# VCFA.net
KiCad netlist of a schematic drawn in EAGLE
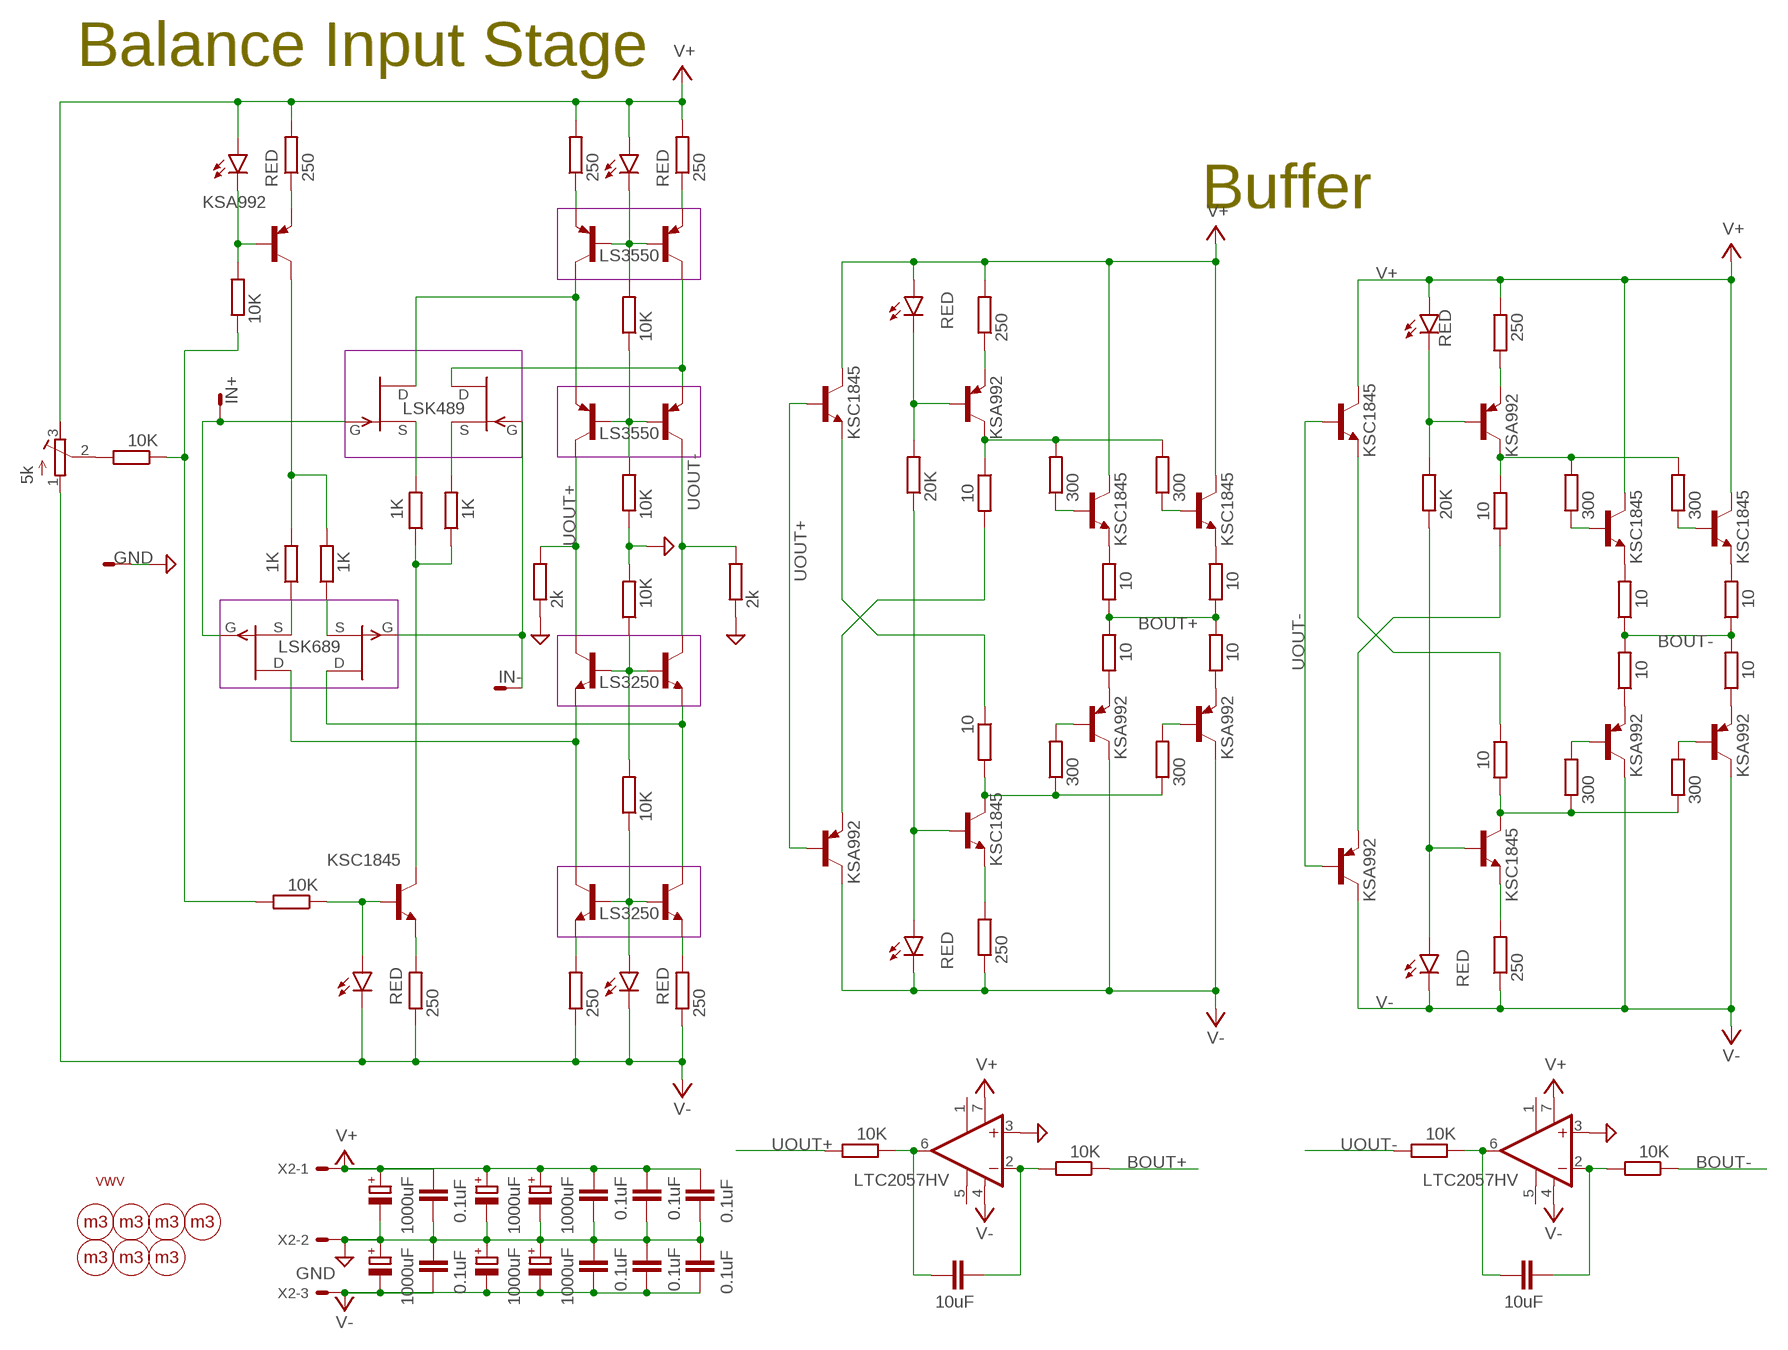
[diagram p0: schematic, sheet 1]
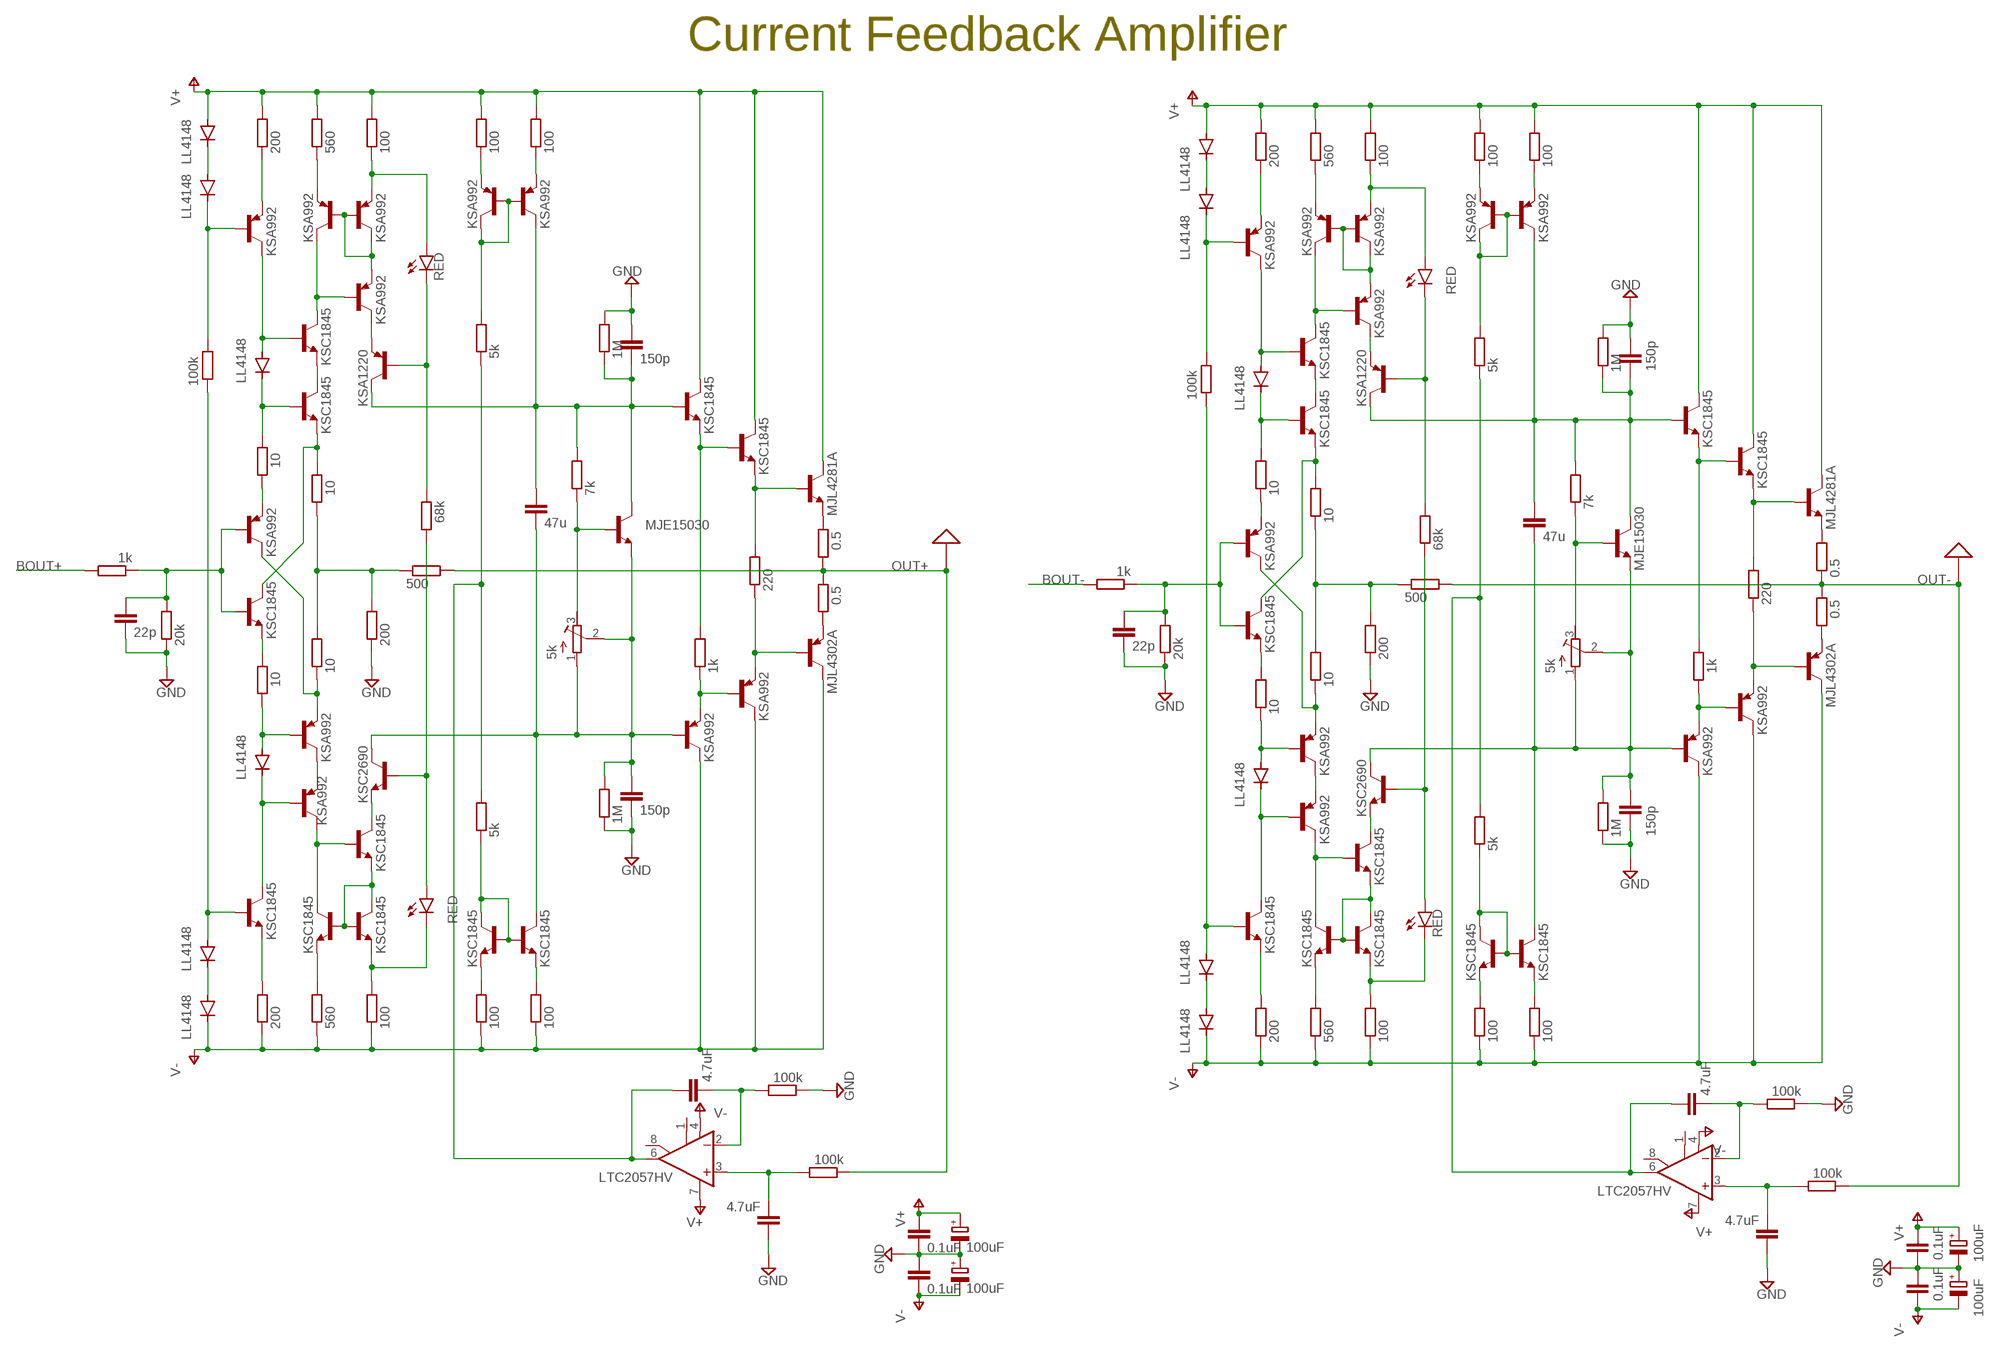
[diagram p1: schematic, sheet 2]
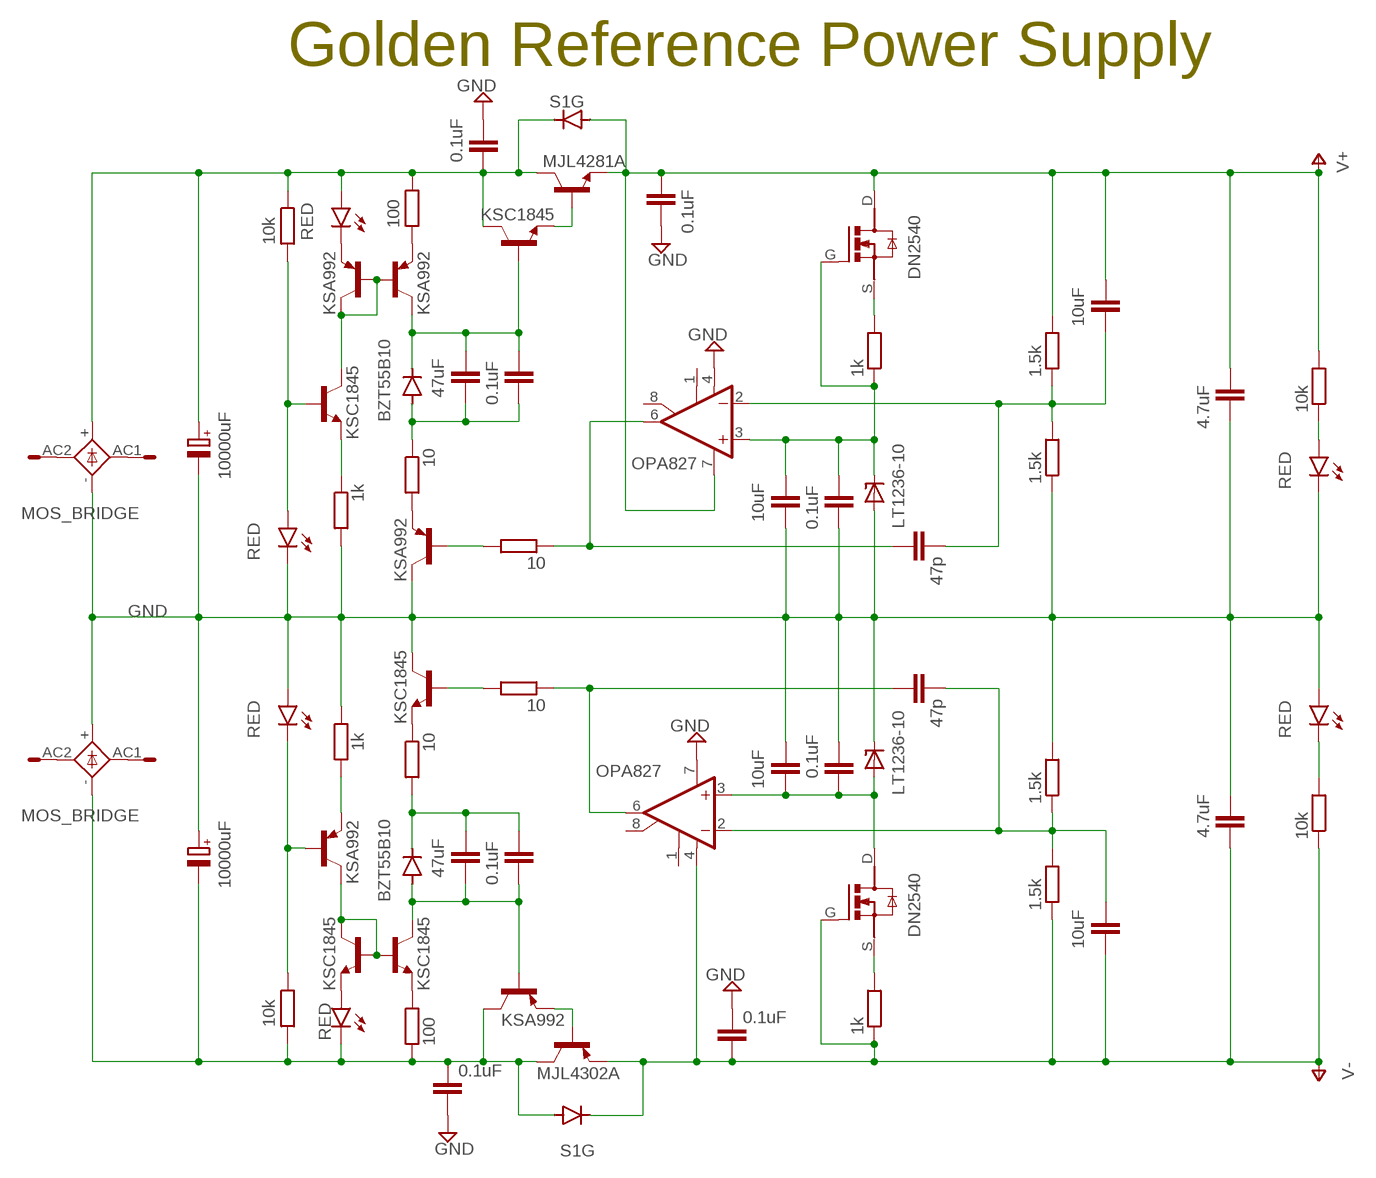
[diagram p2: schematic, sheet 3]

(export (version "E")
  (design (tool "Eeschema 10.0.6"))
  (components
    (comp (ref "C17")
      (value "22p")
      (footprint "eagle-import:C0805")
      (fields (field (name "SPICEPREFIX") "C"))
      (libsource (lib "eagle-import") (part "C-EUC0805"))
    )
    (comp (ref "C18")
      (value "47u")
      (footprint "eagle-import:C1210")
      (fields (field (name "SPICEPREFIX") "C"))
      (libsource (lib "eagle-import") (part "C-EUC1210"))
    )
    (comp (ref "C19")
      (value "150p")
      (footprint "eagle-import:C0805")
      (fields (field (name "SPICEPREFIX") "C"))
      (libsource (lib "eagle-import") (part "C-EUC0805"))
    )
    (comp (ref "C20")
      (value "150p")
      (footprint "eagle-import:C0805")
      (fields (field (name "SPICEPREFIX") "C"))
      (libsource (lib "eagle-import") (part "C-EUC0805"))
    )
    (comp (ref "C21")
      (value "4.7uF")
      (footprint "eagle-import:C1210")
      (fields (field (name "SPICEPREFIX") "C"))
      (libsource (lib "eagle-import") (part "C-EUC1210"))
    )
    (comp (ref "C22")
      (value "4.7uF")
      (footprint "eagle-import:C1210")
      (fields (field (name "SPICEPREFIX") "C"))
      (libsource (lib "eagle-import") (part "C-EUC1210"))
    )
    (comp (ref "C23")
      (value "0.1uF")
      (footprint "eagle-import:C0603K")
      (libsource (lib "eagle-import") (part "C-EUC0603K"))
    )
    (comp (ref "C24")
      (value "0.1uF")
      (footprint "eagle-import:C0603K")
      (libsource (lib "eagle-import") (part "C-EUC0603K"))
    )
    (comp (ref "C25")
      (value "100uF")
      (footprint "eagle-import:E3,5-8")
      (libsource (lib "eagle-import") (part "CPOL-EUE3.5-8"))
    )
    (comp (ref "C26")
      (value "100uF")
      (footprint "eagle-import:E3,5-8")
      (libsource (lib "eagle-import") (part "CPOL-EUE3.5-8"))
    )
    (comp (ref "C27")
      (value "22p")
      (footprint "eagle-import:C0805")
      (fields (field (name "SPICEPREFIX") "C"))
      (libsource (lib "eagle-import") (part "C-EUC0805"))
    )
    (comp (ref "C28")
      (value "47u")
      (footprint "eagle-import:C1210")
      (fields (field (name "SPICEPREFIX") "C"))
      (libsource (lib "eagle-import") (part "C-EUC1210"))
    )
    (comp (ref "C29")
      (value "150p")
      (footprint "eagle-import:C0805")
      (fields (field (name "SPICEPREFIX") "C"))
      (libsource (lib "eagle-import") (part "C-EUC0805"))
    )
    (comp (ref "C30")
      (value "150p")
      (footprint "eagle-import:C0805")
      (fields (field (name "SPICEPREFIX") "C"))
      (libsource (lib "eagle-import") (part "C-EUC0805"))
    )
    (comp (ref "C31")
      (value "4.7uF")
      (footprint "eagle-import:C1210")
      (fields (field (name "SPICEPREFIX") "C"))
      (libsource (lib "eagle-import") (part "C-EUC1210"))
    )
    (comp (ref "C32")
      (value "4.7uF")
      (footprint "eagle-import:C1210")
      (fields (field (name "SPICEPREFIX") "C"))
      (libsource (lib "eagle-import") (part "C-EUC1210"))
    )
    (comp (ref "C33")
      (value "0.1uF")
      (footprint "eagle-import:C0603K")
      (libsource (lib "eagle-import") (part "C-EUC0603K"))
    )
    (comp (ref "C34")
      (value "0.1uF")
      (footprint "eagle-import:C0603K")
      (libsource (lib "eagle-import") (part "C-EUC0603K"))
    )
    (comp (ref "C35")
      (value "100uF")
      (footprint "eagle-import:E3,5-8")
      (libsource (lib "eagle-import") (part "CPOL-EUE3.5-8"))
    )
    (comp (ref "C36")
      (value "100uF")
      (footprint "eagle-import:E3,5-8")
      (libsource (lib "eagle-import") (part "CPOL-EUE3.5-8"))
    )
    (comp (ref "D1")
      (value "LL4148")
      (footprint "eagle-import:SOD80C")
      (fields (field (name "SPICEPREFIX") "D"))
      (libsource (lib "eagle-import") (part "DIODE-SOD80C"))
    )
    (comp (ref "D2")
      (value "LL4148")
      (footprint "eagle-import:SOD80C")
      (fields (field (name "SPICEPREFIX") "D"))
      (libsource (lib "eagle-import") (part "DIODE-SOD80C"))
    )
    (comp (ref "D3")
      (value "LL4148")
      (footprint "eagle-import:SOD80C")
      (fields (field (name "SPICEPREFIX") "D"))
      (libsource (lib "eagle-import") (part "DIODE-SOD80C"))
    )
    (comp (ref "D4")
      (value "LL4148")
      (footprint "eagle-import:SOD80C")
      (fields (field (name "SPICEPREFIX") "D"))
      (libsource (lib "eagle-import") (part "DIODE-SOD80C"))
    )
    (comp (ref "D5")
      (value "LL4148")
      (footprint "eagle-import:SOD80C")
      (fields (field (name "SPICEPREFIX") "D"))
      (libsource (lib "eagle-import") (part "DIODE-SOD80C"))
    )
    (comp (ref "D6")
      (value "LL4148")
      (footprint "eagle-import:SOD80C")
      (fields (field (name "SPICEPREFIX") "D"))
      (libsource (lib "eagle-import") (part "DIODE-SOD80C"))
    )
    (comp (ref "D7")
      (value "LL4148")
      (footprint "eagle-import:SOD80C")
      (fields (field (name "SPICEPREFIX") "D"))
      (libsource (lib "eagle-import") (part "DIODE-SOD80C"))
    )
    (comp (ref "D8")
      (value "LL4148")
      (footprint "eagle-import:SOD80C")
      (fields (field (name "SPICEPREFIX") "D"))
      (libsource (lib "eagle-import") (part "DIODE-SOD80C"))
    )
    (comp (ref "D9")
      (value "LL4148")
      (footprint "eagle-import:SOD80C")
      (fields (field (name "SPICEPREFIX") "D"))
      (libsource (lib "eagle-import") (part "DIODE-SOD80C"))
    )
    (comp (ref "D10")
      (value "LL4148")
      (footprint "eagle-import:SOD80C")
      (fields (field (name "SPICEPREFIX") "D"))
      (libsource (lib "eagle-import") (part "DIODE-SOD80C"))
    )
    (comp (ref "D11")
      (value "LL4148")
      (footprint "eagle-import:SOD80C")
      (fields (field (name "SPICEPREFIX") "D"))
      (libsource (lib "eagle-import") (part "DIODE-SOD80C"))
    )
    (comp (ref "D12")
      (value "LL4148")
      (footprint "eagle-import:SOD80C")
      (fields (field (name "SPICEPREFIX") "D"))
      (libsource (lib "eagle-import") (part "DIODE-SOD80C"))
    )
    (comp (ref "IC3")
      (value "LTC2057HV")
      (footprint "eagle-import:SOIC8")
      (libsource (lib "eagle-import") (part "LT10S837I"))
    )
    (comp (ref "IC4")
      (value "LTC2057HV")
      (footprint "eagle-import:SOIC8")
      (libsource (lib "eagle-import") (part "LT10S837I"))
    )
    (comp (ref "LED9")
      (value "RED")
      (footprint "eagle-import:LED_SML1206")
      (fields (field (name "SPICEPREFIX") "D"))
      (libsource (lib "eagle-import") (part "LEDVWV1206"))
    )
    (comp (ref "LED10")
      (value "RED")
      (footprint "eagle-import:LED_SML1206")
      (fields (field (name "SPICEPREFIX") "D"))
      (libsource (lib "eagle-import") (part "LEDVWV1206"))
    )
    (comp (ref "LED11")
      (value "RED")
      (footprint "eagle-import:LED_SML1206")
      (fields (field (name "SPICEPREFIX") "D"))
      (libsource (lib "eagle-import") (part "LEDVWV1206"))
    )
    (comp (ref "LED12")
      (value "RED")
      (footprint "eagle-import:LED_SML1206")
      (fields (field (name "SPICEPREFIX") "D"))
      (libsource (lib "eagle-import") (part "LEDVWV1206"))
    )
    (comp (ref "PAD1")
      (value "PAD")
      (footprint "eagle-import:PAD-16")
      (libsource (lib "eagle-import") (part "PAD"))
    )
    (comp (ref "PAD2")
      (value "PAD")
      (footprint "eagle-import:PAD-16")
      (libsource (lib "eagle-import") (part "PAD"))
    )
    (comp (ref "Q25")
      (value "KSA992")
      (footprint "eagle-import:TRANSISTOR_TO92-ECB_P")
      (fields (field (name "SPICEPREFIX") "Q"))
      (libsource (lib "eagle-import") (part "BJT_PNPKSA992"))
    )
    (comp (ref "Q26")
      (value "KSA992")
      (footprint "eagle-import:TRANSISTOR_TO92-ECB_P")
      (fields (field (name "SPICEPREFIX") "Q"))
      (libsource (lib "eagle-import") (part "BJT_PNPKSA992"))
    )
    (comp (ref "Q27")
      (value "KSC1845")
      (footprint "eagle-import:TRANSISTOR_TO92-ECB_N")
      (fields (field (name "SPICEPREFIX") "Q"))
      (libsource (lib "eagle-import") (part "BJT_NPNKSC1845"))
    )
    (comp (ref "Q28")
      (value "KSC1845")
      (footprint "eagle-import:TRANSISTOR_TO92-ECB_N")
      (fields (field (name "SPICEPREFIX") "Q"))
      (libsource (lib "eagle-import") (part "BJT_NPNKSC1845"))
    )
    (comp (ref "Q29")
      (value "KSC1845")
      (footprint "eagle-import:TRANSISTOR_TO92-ECB_N")
      (fields (field (name "SPICEPREFIX") "Q"))
      (libsource (lib "eagle-import") (part "BJT_NPNKSC1845"))
    )
    (comp (ref "Q30")
      (value "KSC1845")
      (footprint "eagle-import:TRANSISTOR_TO92-ECB_N")
      (fields (field (name "SPICEPREFIX") "Q"))
      (libsource (lib "eagle-import") (part "BJT_NPNKSC1845"))
    )
    (comp (ref "Q31")
      (value "KSA992")
      (footprint "eagle-import:TRANSISTOR_TO92-ECB_P")
      (fields (field (name "SPICEPREFIX") "Q"))
      (libsource (lib "eagle-import") (part "BJT_PNPKSA992"))
    )
    (comp (ref "Q32")
      (value "KSA992")
      (footprint "eagle-import:TRANSISTOR_TO92-ECB_P")
      (fields (field (name "SPICEPREFIX") "Q"))
      (libsource (lib "eagle-import") (part "BJT_PNPKSA992"))
    )
    (comp (ref "Q33")
      (value "KSA992")
      (footprint "eagle-import:TRANSISTOR_TO92-ECB_P")
      (fields (field (name "SPICEPREFIX") "Q"))
      (libsource (lib "eagle-import") (part "BJT_PNPKSA992"))
    )
    (comp (ref "Q34")
      (value "KSC1845")
      (footprint "eagle-import:TRANSISTOR_TO92-ECB_N")
      (fields (field (name "SPICEPREFIX") "Q"))
      (libsource (lib "eagle-import") (part "BJT_NPNKSC1845"))
    )
    (comp (ref "Q35")
      (value "KSA992")
      (footprint "eagle-import:TRANSISTOR_TO92-ECB_P")
      (fields (field (name "SPICEPREFIX") "Q"))
      (libsource (lib "eagle-import") (part "BJT_PNPKSA992"))
    )
    (comp (ref "Q36")
      (value "KSA992")
      (footprint "eagle-import:TRANSISTOR_TO92-ECB_P")
      (fields (field (name "SPICEPREFIX") "Q"))
      (libsource (lib "eagle-import") (part "BJT_PNPKSA992"))
    )
    (comp (ref "Q37")
      (value "KSC1845")
      (footprint "eagle-import:TRANSISTOR_TO92-ECB_N")
      (fields (field (name "SPICEPREFIX") "Q"))
      (libsource (lib "eagle-import") (part "BJT_NPNKSC1845"))
    )
    (comp (ref "Q38")
      (value "KSC1845")
      (footprint "eagle-import:TRANSISTOR_TO92-ECB_N")
      (fields (field (name "SPICEPREFIX") "Q"))
      (libsource (lib "eagle-import") (part "BJT_NPNKSC1845"))
    )
    (comp (ref "Q39")
      (value "KSA1220")
      (footprint "eagle-import:TRANSISTOR_TO126_P")
      (fields (field (name "SPICEPREFIX") "Q"))
      (libsource (lib "eagle-import") (part "BJT_PNPKSA1220"))
    )
    (comp (ref "Q40")
      (value "KSC2690")
      (footprint "eagle-import:TRANSISTOR_TO126_N")
      (fields (field (name "SPICEPREFIX") "Q"))
      (libsource (lib "eagle-import") (part "BJT_NPNKSC2690"))
    )
    (comp (ref "Q41")
      (value "KSA992")
      (footprint "eagle-import:TRANSISTOR_TO92-ECB_P")
      (fields (field (name "SPICEPREFIX") "Q"))
      (libsource (lib "eagle-import") (part "BJT_PNPKSA992"))
    )
    (comp (ref "Q42")
      (value "KSC1845")
      (footprint "eagle-import:TRANSISTOR_TO92-ECB_N")
      (fields (field (name "SPICEPREFIX") "Q"))
      (libsource (lib "eagle-import") (part "BJT_NPNKSC1845"))
    )
    (comp (ref "Q43")
      (value "KSA992")
      (footprint "eagle-import:TRANSISTOR_TO92-ECB_P")
      (fields (field (name "SPICEPREFIX") "Q"))
      (libsource (lib "eagle-import") (part "BJT_PNPKSA992"))
    )
    (comp (ref "Q44")
      (value "KSC1845")
      (footprint "eagle-import:TRANSISTOR_TO92-ECB_N")
      (fields (field (name "SPICEPREFIX") "Q"))
      (libsource (lib "eagle-import") (part "BJT_NPNKSC1845"))
    )
    (comp (ref "Q45")
      (value "MJE15030")
      (footprint "eagle-import:TRANSISTOR_TO220_BCE_N")
      (fields (field (name "SPICEPREFIX") "Q"))
      (libsource (lib "eagle-import") (part "BJT_NPNMJE15030"))
    )
    (comp (ref "Q46")
      (value "KSC1845")
      (footprint "eagle-import:TRANSISTOR_TO92-ECB_N")
      (fields (field (name "SPICEPREFIX") "Q"))
      (libsource (lib "eagle-import") (part "BJT_NPNKSC1845"))
    )
    (comp (ref "Q47")
      (value "KSA992")
      (footprint "eagle-import:TRANSISTOR_TO92-ECB_P")
      (fields (field (name "SPICEPREFIX") "Q"))
      (libsource (lib "eagle-import") (part "BJT_PNPKSA992"))
    )
    (comp (ref "Q48")
      (value "KSC1845")
      (footprint "eagle-import:TRANSISTOR_TO92-ECB_N")
      (fields (field (name "SPICEPREFIX") "Q"))
      (libsource (lib "eagle-import") (part "BJT_NPNKSC1845"))
    )
    (comp (ref "Q49")
      (value "KSA992")
      (footprint "eagle-import:TRANSISTOR_TO92-ECB_P")
      (fields (field (name "SPICEPREFIX") "Q"))
      (libsource (lib "eagle-import") (part "BJT_PNPKSA992"))
    )
    (comp (ref "Q50")
      (value "MJL4281A")
      (footprint "eagle-import:TRANSISTOR_TO247_BCE_N")
      (fields (field (name "SPICEPREFIX") "Q"))
      (libsource (lib "eagle-import") (part "BJT_NPNMJL4281"))
    )
    (comp (ref "Q51")
      (value "MJL4302A")
      (footprint "eagle-import:TRANSISTOR_TO247_BCE_P")
      (fields (field (name "SPICEPREFIX") "Q"))
      (libsource (lib "eagle-import") (part "BJT_PNPMJL4302"))
    )
    (comp (ref "Q52")
      (value "KSA992")
      (footprint "eagle-import:TRANSISTOR_TO92-ECB_P")
      (fields (field (name "SPICEPREFIX") "Q"))
      (libsource (lib "eagle-import") (part "BJT_PNPKSA992"))
    )
    (comp (ref "Q53")
      (value "KSA992")
      (footprint "eagle-import:TRANSISTOR_TO92-ECB_P")
      (fields (field (name "SPICEPREFIX") "Q"))
      (libsource (lib "eagle-import") (part "BJT_PNPKSA992"))
    )
    (comp (ref "Q54")
      (value "KSC1845")
      (footprint "eagle-import:TRANSISTOR_TO92-ECB_N")
      (fields (field (name "SPICEPREFIX") "Q"))
      (libsource (lib "eagle-import") (part "BJT_NPNKSC1845"))
    )
    (comp (ref "Q55")
      (value "KSC1845")
      (footprint "eagle-import:TRANSISTOR_TO92-ECB_N")
      (fields (field (name "SPICEPREFIX") "Q"))
      (libsource (lib "eagle-import") (part "BJT_NPNKSC1845"))
    )
    (comp (ref "Q56")
      (value "KSC1845")
      (footprint "eagle-import:TRANSISTOR_TO92-ECB_N")
      (fields (field (name "SPICEPREFIX") "Q"))
      (libsource (lib "eagle-import") (part "BJT_NPNKSC1845"))
    )
    (comp (ref "Q57")
      (value "KSC1845")
      (footprint "eagle-import:TRANSISTOR_TO92-ECB_N")
      (fields (field (name "SPICEPREFIX") "Q"))
      (libsource (lib "eagle-import") (part "BJT_NPNKSC1845"))
    )
    (comp (ref "Q58")
      (value "KSA992")
      (footprint "eagle-import:TRANSISTOR_TO92-ECB_P")
      (fields (field (name "SPICEPREFIX") "Q"))
      (libsource (lib "eagle-import") (part "BJT_PNPKSA992"))
    )
    (comp (ref "Q59")
      (value "KSA992")
      (footprint "eagle-import:TRANSISTOR_TO92-ECB_P")
      (fields (field (name "SPICEPREFIX") "Q"))
      (libsource (lib "eagle-import") (part "BJT_PNPKSA992"))
    )
    (comp (ref "Q60")
      (value "KSA992")
      (footprint "eagle-import:TRANSISTOR_TO92-ECB_P")
      (fields (field (name "SPICEPREFIX") "Q"))
      (libsource (lib "eagle-import") (part "BJT_PNPKSA992"))
    )
    (comp (ref "Q61")
      (value "KSC1845")
      (footprint "eagle-import:TRANSISTOR_TO92-ECB_N")
      (fields (field (name "SPICEPREFIX") "Q"))
      (libsource (lib "eagle-import") (part "BJT_NPNKSC1845"))
    )
    (comp (ref "Q62")
      (value "KSA992")
      (footprint "eagle-import:TRANSISTOR_TO92-ECB_P")
      (fields (field (name "SPICEPREFIX") "Q"))
      (libsource (lib "eagle-import") (part "BJT_PNPKSA992"))
    )
    (comp (ref "Q63")
      (value "KSA992")
      (footprint "eagle-import:TRANSISTOR_TO92-ECB_P")
      (fields (field (name "SPICEPREFIX") "Q"))
      (libsource (lib "eagle-import") (part "BJT_PNPKSA992"))
    )
    (comp (ref "Q64")
      (value "KSC1845")
      (footprint "eagle-import:TRANSISTOR_TO92-ECB_N")
      (fields (field (name "SPICEPREFIX") "Q"))
      (libsource (lib "eagle-import") (part "BJT_NPNKSC1845"))
    )
    (comp (ref "Q65")
      (value "KSC1845")
      (footprint "eagle-import:TRANSISTOR_TO92-ECB_N")
      (fields (field (name "SPICEPREFIX") "Q"))
      (libsource (lib "eagle-import") (part "BJT_NPNKSC1845"))
    )
    (comp (ref "Q66")
      (value "KSA1220")
      (footprint "eagle-import:TRANSISTOR_TO126_P")
      (fields (field (name "SPICEPREFIX") "Q"))
      (libsource (lib "eagle-import") (part "BJT_PNPKSA1220"))
    )
    (comp (ref "Q67")
      (value "KSC2690")
      (footprint "eagle-import:TRANSISTOR_TO126_N")
      (fields (field (name "SPICEPREFIX") "Q"))
      (libsource (lib "eagle-import") (part "BJT_NPNKSC2690"))
    )
    (comp (ref "Q68")
      (value "KSA992")
      (footprint "eagle-import:TRANSISTOR_TO92-ECB_P")
      (fields (field (name "SPICEPREFIX") "Q"))
      (libsource (lib "eagle-import") (part "BJT_PNPKSA992"))
    )
    (comp (ref "Q69")
      (value "KSC1845")
      (footprint "eagle-import:TRANSISTOR_TO92-ECB_N")
      (fields (field (name "SPICEPREFIX") "Q"))
      (libsource (lib "eagle-import") (part "BJT_NPNKSC1845"))
    )
    (comp (ref "Q70")
      (value "KSA992")
      (footprint "eagle-import:TRANSISTOR_TO92-ECB_P")
      (fields (field (name "SPICEPREFIX") "Q"))
      (libsource (lib "eagle-import") (part "BJT_PNPKSA992"))
    )
    (comp (ref "Q71")
      (value "KSC1845")
      (footprint "eagle-import:TRANSISTOR_TO92-ECB_N")
      (fields (field (name "SPICEPREFIX") "Q"))
      (libsource (lib "eagle-import") (part "BJT_NPNKSC1845"))
    )
    (comp (ref "Q72")
      (value "MJE15030")
      (footprint "eagle-import:TRANSISTOR_TO220_BCE_N")
      (fields (field (name "SPICEPREFIX") "Q"))
      (libsource (lib "eagle-import") (part "BJT_NPNMJE15030"))
    )
    (comp (ref "Q73")
      (value "KSC1845")
      (footprint "eagle-import:TRANSISTOR_TO92-ECB_N")
      (fields (field (name "SPICEPREFIX") "Q"))
      (libsource (lib "eagle-import") (part "BJT_NPNKSC1845"))
    )
    (comp (ref "Q74")
      (value "KSA992")
      (footprint "eagle-import:TRANSISTOR_TO92-ECB_P")
      (fields (field (name "SPICEPREFIX") "Q"))
      (libsource (lib "eagle-import") (part "BJT_PNPKSA992"))
    )
    (comp (ref "Q75")
      (value "KSC1845")
      (footprint "eagle-import:TRANSISTOR_TO92-ECB_N")
      (fields (field (name "SPICEPREFIX") "Q"))
      (libsource (lib "eagle-import") (part "BJT_NPNKSC1845"))
    )
    (comp (ref "Q76")
      (value "KSA992")
      (footprint "eagle-import:TRANSISTOR_TO92-ECB_P")
      (fields (field (name "SPICEPREFIX") "Q"))
      (libsource (lib "eagle-import") (part "BJT_PNPKSA992"))
    )
    (comp (ref "Q77")
      (value "MJL4281A")
      (footprint "eagle-import:TRANSISTOR_TO247_BCE_N")
      (fields (field (name "SPICEPREFIX") "Q"))
      (libsource (lib "eagle-import") (part "BJT_NPNMJL4281"))
    )
    (comp (ref "Q78")
      (value "MJL4302A")
      (footprint "eagle-import:TRANSISTOR_TO247_BCE_P")
      (fields (field (name "SPICEPREFIX") "Q"))
      (libsource (lib "eagle-import") (part "BJT_PNPMJL4302"))
    )
    (comp (ref "R51")
      (value "1k")
      (footprint "eagle-import:MINI_MELF-0204W")
      (fields (field (name "SPICEPREFIX") "R"))
      (libsource (lib "eagle-import") (part "R-EU_MELF0204W"))
    )
    (comp (ref "R52")
      (value "20k")
      (footprint "eagle-import:MINI_MELF-0204W")
      (fields (field (name "SPICEPREFIX") "R"))
      (libsource (lib "eagle-import") (part "R-EU_MELF0204W"))
    )
    (comp (ref "R53")
      (value "100k")
      (footprint "eagle-import:MINI_MELF-0204W")
      (fields (field (name "SPICEPREFIX") "R"))
      (libsource (lib "eagle-import") (part "R-EU_MELF0204W"))
    )
    (comp (ref "R54")
      (value "200")
      (footprint "eagle-import:MINI_MELF-0204W")
      (fields (field (name "SPICEPREFIX") "R"))
      (libsource (lib "eagle-import") (part "R-EU_MELF0204W"))
    )
    (comp (ref "R55")
      (value "10")
      (footprint "eagle-import:MINI_MELF-0204W")
      (fields (field (name "SPICEPREFIX") "R"))
      (libsource (lib "eagle-import") (part "R-EU_MELF0204W"))
    )
    (comp (ref "R56")
      (value "10")
      (footprint "eagle-import:MINI_MELF-0204W")
      (fields (field (name "SPICEPREFIX") "R"))
      (libsource (lib "eagle-import") (part "R-EU_MELF0204W"))
    )
    (comp (ref "R57")
      (value "200")
      (footprint "eagle-import:MINI_MELF-0204W")
      (fields (field (name "SPICEPREFIX") "R"))
      (libsource (lib "eagle-import") (part "R-EU_MELF0204W"))
    )
    (comp (ref "R58")
      (value "560")
      (footprint "eagle-import:MINI_MELF-0204W")
      (fields (field (name "SPICEPREFIX") "R"))
      (libsource (lib "eagle-import") (part "R-EU_MELF0204W"))
    )
    (comp (ref "R59")
      (value "10")
      (footprint "eagle-import:MINI_MELF-0204W")
      (fields (field (name "SPICEPREFIX") "R"))
      (libsource (lib "eagle-import") (part "R-EU_MELF0204W"))
    )
    (comp (ref "R60")
      (value "10")
      (footprint "eagle-import:MINI_MELF-0204W")
      (fields (field (name "SPICEPREFIX") "R"))
      (libsource (lib "eagle-import") (part "R-EU_MELF0204W"))
    )
    (comp (ref "R61")
      (value "560")
      (footprint "eagle-import:MINI_MELF-0204W")
      (fields (field (name "SPICEPREFIX") "R"))
      (libsource (lib "eagle-import") (part "R-EU_MELF0204W"))
    )
    (comp (ref "R62")
      (value "100")
      (footprint "eagle-import:MINI_MELF-0204W")
      (fields (field (name "SPICEPREFIX") "R"))
      (libsource (lib "eagle-import") (part "R-EU_MELF0204W"))
    )
    (comp (ref "R63")
      (value "200")
      (footprint "eagle-import:MINI_MELF-0204W")
      (fields (field (name "SPICEPREFIX") "R"))
      (libsource (lib "eagle-import") (part "R-EU_MELF0204W"))
    )
    (comp (ref "R64")
      (value "100")
      (footprint "eagle-import:MINI_MELF-0204W")
      (fields (field (name "SPICEPREFIX") "R"))
      (libsource (lib "eagle-import") (part "R-EU_MELF0204W"))
    )
    (comp (ref "R65")
      (value "68k")
      (footprint "eagle-import:MINI_MELF-0204W")
      (fields (field (name "SPICEPREFIX") "R"))
      (libsource (lib "eagle-import") (part "R-EU_MELF0204W"))
    )
    (comp (ref "R66")
      (value "500")
      (footprint "eagle-import:MINI_MELF-0204W")
      (fields (field (name "SPICEPREFIX") "R"))
      (libsource (lib "eagle-import") (part "R-EU_MELF0204W"))
    )
    (comp (ref "R67")
      (value "100")
      (footprint "eagle-import:MINI_MELF-0204W")
      (fields (field (name "SPICEPREFIX") "R"))
      (libsource (lib "eagle-import") (part "R-EU_MELF0204W"))
    )
    (comp (ref "R68")
      (value "5k")
      (footprint "eagle-import:MINI_MELF-0204W")
      (fields (field (name "SPICEPREFIX") "R"))
      (libsource (lib "eagle-import") (part "R-EU_MELF0204W"))
    )
    (comp (ref "R69")
      (value "5k")
      (footprint "eagle-import:MINI_MELF-0204W")
      (fields (field (name "SPICEPREFIX") "R"))
      (libsource (lib "eagle-import") (part "R-EU_MELF0204W"))
    )
    (comp (ref "R70")
      (value "100")
      (footprint "eagle-import:MINI_MELF-0204W")
      (fields (field (name "SPICEPREFIX") "R"))
      (libsource (lib "eagle-import") (part "R-EU_MELF0204W"))
    )
    (comp (ref "R71")
      (value "100")
      (footprint "eagle-import:MINI_MELF-0204W")
      (fields (field (name "SPICEPREFIX") "R"))
      (libsource (lib "eagle-import") (part "R-EU_MELF0204W"))
    )
    (comp (ref "R72")
      (value "100")
      (footprint "eagle-import:MINI_MELF-0204W")
      (fields (field (name "SPICEPREFIX") "R"))
      (libsource (lib "eagle-import") (part "R-EU_MELF0204W"))
    )
    (comp (ref "R73")
      (value "7k")
      (footprint "eagle-import:MINI_MELF-0204W")
      (fields (field (name "SPICEPREFIX") "R"))
      (libsource (lib "eagle-import") (part "R-EU_MELF0204W"))
    )
    (comp (ref "R74")
      (value "5k")
      (footprint "eagle-import:RTRIM3296W")
      (fields (field (name "SPICEPREFIX") "Z"))
      (libsource (lib "eagle-import") (part "R-TRIMM3296W"))
    )
    (comp (ref "R75")
      (value "1M")
      (footprint "eagle-import:MINI_MELF-0204W")
      (fields (field (name "SPICEPREFIX") "R"))
      (libsource (lib "eagle-import") (part "R-EU_MELF0204W"))
    )
    (comp (ref "R76")
      (value "1M")
      (footprint "eagle-import:MINI_MELF-0204W")
      (fields (field (name "SPICEPREFIX") "R"))
      (libsource (lib "eagle-import") (part "R-EU_MELF0204W"))
    )
    (comp (ref "R77")
      (value "1k")
      (footprint "eagle-import:MINI_MELF-0204W")
      (fields (field (name "SPICEPREFIX") "R"))
      (libsource (lib "eagle-import") (part "R-EU_MELF0204W"))
    )
    (comp (ref "R78")
      (value "220")
      (footprint "eagle-import:MINI_MELF-0204W")
      (fields (field (name "SPICEPREFIX") "R"))
      (libsource (lib "eagle-import") (part "R-EU_MELF0204W"))
    )
    (comp (ref "R79")
      (value "100k")
      (footprint "eagle-import:MINI_MELF-0204W")
      (fields (field (name "SPICEPREFIX") "R"))
      (libsource (lib "eagle-import") (part "R-EU_MELF0204W"))
    )
    (comp (ref "R80")
      (value "0.5")
      (footprint "eagle-import:R2512")
      (fields (field (name "SPICEPREFIX") "R"))
      (libsource (lib "eagle-import") (part "R-EU_R2512"))
    )
    (comp (ref "R81")
      (value "0.5")
      (footprint "eagle-import:R2512")
      (fields (field (name "SPICEPREFIX") "R"))
      (libsource (lib "eagle-import") (part "R-EU_R2512"))
    )
    (comp (ref "R82")
      (value "100k")
      (footprint "eagle-import:MINI_MELF-0204W")
      (fields (field (name "SPICEPREFIX") "R"))
      (libsource (lib "eagle-import") (part "R-EU_MELF0204W"))
    )
    (comp (ref "R83")
      (value "1k")
      (footprint "eagle-import:MINI_MELF-0204W")
      (fields (field (name "SPICEPREFIX") "R"))
      (libsource (lib "eagle-import") (part "R-EU_MELF0204W"))
    )
    (comp (ref "R84")
      (value "20k")
      (footprint "eagle-import:MINI_MELF-0204W")
      (fields (field (name "SPICEPREFIX") "R"))
      (libsource (lib "eagle-import") (part "R-EU_MELF0204W"))
    )
    (comp (ref "R85")
      (value "100k")
      (footprint "eagle-import:MINI_MELF-0204W")
      (fields (field (name "SPICEPREFIX") "R"))
      (libsource (lib "eagle-import") (part "R-EU_MELF0204W"))
    )
    (comp (ref "R86")
      (value "200")
      (footprint "eagle-import:MINI_MELF-0204W")
      (fields (field (name "SPICEPREFIX") "R"))
      (libsource (lib "eagle-import") (part "R-EU_MELF0204W"))
    )
    (comp (ref "R87")
      (value "10")
      (footprint "eagle-import:MINI_MELF-0204W")
      (fields (field (name "SPICEPREFIX") "R"))
      (libsource (lib "eagle-import") (part "R-EU_MELF0204W"))
    )
    (comp (ref "R88")
      (value "10")
      (footprint "eagle-import:MINI_MELF-0204W")
      (fields (field (name "SPICEPREFIX") "R"))
      (libsource (lib "eagle-import") (part "R-EU_MELF0204W"))
    )
    (comp (ref "R89")
      (value "200")
      (footprint "eagle-import:MINI_MELF-0204W")
      (fields (field (name "SPICEPREFIX") "R"))
      (libsource (lib "eagle-import") (part "R-EU_MELF0204W"))
    )
    (comp (ref "R90")
      (value "560")
      (footprint "eagle-import:MINI_MELF-0204W")
      (fields (field (name "SPICEPREFIX") "R"))
      (libsource (lib "eagle-import") (part "R-EU_MELF0204W"))
    )
    (comp (ref "R91")
      (value "10")
      (footprint "eagle-import:MINI_MELF-0204W")
      (fields (field (name "SPICEPREFIX") "R"))
      (libsource (lib "eagle-import") (part "R-EU_MELF0204W"))
    )
    (comp (ref "R92")
      (value "10")
      (footprint "eagle-import:MINI_MELF-0204W")
      (fields (field (name "SPICEPREFIX") "R"))
      (libsource (lib "eagle-import") (part "R-EU_MELF0204W"))
    )
    (comp (ref "R93")
      (value "560")
      (footprint "eagle-import:MINI_MELF-0204W")
      (fields (field (name "SPICEPREFIX") "R"))
      (libsource (lib "eagle-import") (part "R-EU_MELF0204W"))
    )
    (comp (ref "R94")
      (value "100")
      (footprint "eagle-import:MINI_MELF-0204W")
      (fields (field (name "SPICEPREFIX") "R"))
      (libsource (lib "eagle-import") (part "R-EU_MELF0204W"))
    )
    (comp (ref "R95")
      (value "200")
      (footprint "eagle-import:MINI_MELF-0204W")
      (fields (field (name "SPICEPREFIX") "R"))
      (libsource (lib "eagle-import") (part "R-EU_MELF0204W"))
    )
    (comp (ref "R96")
      (value "100")
      (footprint "eagle-import:MINI_MELF-0204W")
      (fields (field (name "SPICEPREFIX") "R"))
      (libsource (lib "eagle-import") (part "R-EU_MELF0204W"))
    )
    (comp (ref "R97")
      (value "68k")
      (footprint "eagle-import:MINI_MELF-0204W")
      (fields (field (name "SPICEPREFIX") "R"))
      (libsource (lib "eagle-import") (part "R-EU_MELF0204W"))
    )
    (comp (ref "R98")
      (value "500")
      (footprint "eagle-import:MINI_MELF-0204W")
      (fields (field (name "SPICEPREFIX") "R"))
      (libsource (lib "eagle-import") (part "R-EU_MELF0204W"))
    )
    (comp (ref "R99")
      (value "100")
      (footprint "eagle-import:MINI_MELF-0204W")
      (fields (field (name "SPICEPREFIX") "R"))
      (libsource (lib "eagle-import") (part "R-EU_MELF0204W"))
    )
    (comp (ref "R100")
      (value "5k")
      (footprint "eagle-import:MINI_MELF-0204W")
      (fields (field (name "SPICEPREFIX") "R"))
      (libsource (lib "eagle-import") (part "R-EU_MELF0204W"))
    )
    (comp (ref "R101")
      (value "5k")
      (footprint "eagle-import:MINI_MELF-0204W")
      (fields (field (name "SPICEPREFIX") "R"))
      (libsource (lib "eagle-import") (part "R-EU_MELF0204W"))
    )
    (comp (ref "R102")
      (value "100")
      (footprint "eagle-import:MINI_MELF-0204W")
      (fields (field (name "SPICEPREFIX") "R"))
      (libsource (lib "eagle-import") (part "R-EU_MELF0204W"))
    )
    (comp (ref "R103")
      (value "100")
      (footprint "eagle-import:MINI_MELF-0204W")
      (fields (field (name "SPICEPREFIX") "R"))
      (libsource (lib "eagle-import") (part "R-EU_MELF0204W"))
    )
    (comp (ref "R104")
      (value "100")
      (footprint "eagle-import:MINI_MELF-0204W")
      (fields (field (name "SPICEPREFIX") "R"))
      (libsource (lib "eagle-import") (part "R-EU_MELF0204W"))
    )
    (comp (ref "R105")
      (value "7k")
      (footprint "eagle-import:MINI_MELF-0204W")
      (fields (field (name "SPICEPREFIX") "R"))
      (libsource (lib "eagle-import") (part "R-EU_MELF0204W"))
    )
    (comp (ref "R106")
      (value "5k")
      (footprint "eagle-import:RTRIM3296W")
      (fields (field (name "SPICEPREFIX") "Z"))
      (libsource (lib "eagle-import") (part "R-TRIMM3296W"))
    )
    (comp (ref "R107")
      (value "1M")
      (footprint "eagle-import:MINI_MELF-0204W")
      (fields (field (name "SPICEPREFIX") "R"))
      (libsource (lib "eagle-import") (part "R-EU_MELF0204W"))
    )
    (comp (ref "R108")
      (value "1M")
      (footprint "eagle-import:MINI_MELF-0204W")
      (fields (field (name "SPICEPREFIX") "R"))
      (libsource (lib "eagle-import") (part "R-EU_MELF0204W"))
    )
    (comp (ref "R109")
      (value "1k")
      (footprint "eagle-import:MINI_MELF-0204W")
      (fields (field (name "SPICEPREFIX") "R"))
      (libsource (lib "eagle-import") (part "R-EU_MELF0204W"))
    )
    (comp (ref "R110")
      (value "220")
      (footprint "eagle-import:MINI_MELF-0204W")
      (fields (field (name "SPICEPREFIX") "R"))
      (libsource (lib "eagle-import") (part "R-EU_MELF0204W"))
    )
    (comp (ref "R111")
      (value "100k")
      (footprint "eagle-import:MINI_MELF-0204W")
      (fields (field (name "SPICEPREFIX") "R"))
      (libsource (lib "eagle-import") (part "R-EU_MELF0204W"))
    )
    (comp (ref "R112")
      (value "0.5")
      (footprint "eagle-import:R2512")
      (fields (field (name "SPICEPREFIX") "R"))
      (libsource (lib "eagle-import") (part "R-EU_R2512"))
    )
    (comp (ref "R113")
      (value "0.5")
      (footprint "eagle-import:R2512")
      (fields (field (name "SPICEPREFIX") "R"))
      (libsource (lib "eagle-import") (part "R-EU_R2512"))
    )
    (comp (ref "R114")
      (value "100k")
      (footprint "eagle-import:MINI_MELF-0204W")
      (fields (field (name "SPICEPREFIX") "R"))
      (libsource (lib "eagle-import") (part "R-EU_MELF0204W"))
    )
    (comp (ref "C1")
      (value "1000uF")
      (footprint "eagle-import:E7,5-16")
      (libsource (lib "eagle-import") (part "CPOL-EUE7.5-16"))
    )
    (comp (ref "C2")
      (value "1000uF")
      (footprint "eagle-import:E7,5-16")
      (libsource (lib "eagle-import") (part "CPOL-EUE7.5-16"))
    )
    (comp (ref "C3")
      (value "0.1uF")
      (footprint "eagle-import:C0805")
      (libsource (lib "eagle-import") (part "C-EUC0805"))
    )
    (comp (ref "C4")
      (value "0.1uF")
      (footprint "eagle-import:C0805")
      (libsource (lib "eagle-import") (part "C-EUC0805"))
    )
    (comp (ref "C5")
      (value "1000uF")
      (footprint "eagle-import:E7,5-16")
      (libsource (lib "eagle-import") (part "CPOL-EUE7.5-16"))
    )
    (comp (ref "C6")
      (value "1000uF")
      (footprint "eagle-import:E7,5-16")
      (libsource (lib "eagle-import") (part "CPOL-EUE7.5-16"))
    )
    (comp (ref "C7")
      (value "1000uF")
      (footprint "eagle-import:E7,5-16")
      (libsource (lib "eagle-import") (part "CPOL-EUE7.5-16"))
    )
    (comp (ref "C8")
      (value "1000uF")
      (footprint "eagle-import:E7,5-16")
      (libsource (lib "eagle-import") (part "CPOL-EUE7.5-16"))
    )
    (comp (ref "C9")
      (value "0.1uF")
      (footprint "eagle-import:C050-045X075")
      (libsource (lib "eagle-import") (part "C-EU050-045X075"))
    )
    (comp (ref "C10")
      (value "0.1uF")
      (footprint "eagle-import:C050-045X075")
      (libsource (lib "eagle-import") (part "C-EU050-045X075"))
    )
    (comp (ref "C11")
      (value "0.1uF")
      (footprint "eagle-import:C050-045X075")
      (libsource (lib "eagle-import") (part "C-EU050-045X075"))
    )
    (comp (ref "C12")
      (value "0.1uF")
      (footprint "eagle-import:C050-045X075")
      (libsource (lib "eagle-import") (part "C-EU050-045X075"))
    )
    (comp (ref "C13")
      (value "10uF")
      (footprint "eagle-import:C1206")
      (libsource (lib "eagle-import") (part "C-EUC1206"))
    )
    (comp (ref "C14")
      (value "0.1uF")
      (footprint "eagle-import:C0805")
      (libsource (lib "eagle-import") (part "C-EUC0805"))
    )
    (comp (ref "C15")
      (value "0.1uF")
      (footprint "eagle-import:C0805")
      (libsource (lib "eagle-import") (part "C-EUC0805"))
    )
    (comp (ref "C16")
      (value "10uF")
      (footprint "eagle-import:C1206")
      (libsource (lib "eagle-import") (part "C-EUC1206"))
    )
    (comp (ref "H1")
      (value "HOLE")
      (footprint "eagle-import:M3_HOLE")
      (libsource (lib "eagle-import") (part "HOLE"))
    )
    (comp (ref "H2")
      (value "HOLE")
      (footprint "eagle-import:M3_HOLE")
      (libsource (lib "eagle-import") (part "HOLE"))
    )
    (comp (ref "H3")
      (value "HOLE")
      (footprint "eagle-import:M3_HOLE")
      (libsource (lib "eagle-import") (part "HOLE"))
    )
    (comp (ref "H4")
      (value "HOLE")
      (footprint "eagle-import:M3_HOLE")
      (libsource (lib "eagle-import") (part "HOLE"))
    )
    (comp (ref "H5")
      (value "HOLE")
      (footprint "eagle-import:M3_HOLE")
      (libsource (lib "eagle-import") (part "HOLE"))
    )
    (comp (ref "H6")
      (value "HOLE")
      (footprint "eagle-import:M3_HOLE")
      (libsource (lib "eagle-import") (part "HOLE"))
    )
    (comp (ref "H7")
      (value "HOLE")
      (footprint "eagle-import:M3_HOLE")
      (libsource (lib "eagle-import") (part "HOLE"))
    )
    (comp (ref "IC1")
      (value "LTC2057HV")
      (footprint "eagle-import:SO08")
      (fields (field (name "MF") "TEXAS INSTRUMENTS") (field (name "MPN") "OPA627AU"))
      (libsource (lib "eagle-import") (part "OPA627U"))
    )
    (comp (ref "IC2")
      (value "LTC2057HV")
      (footprint "eagle-import:SO08")
      (fields (field (name "MF") "TEXAS INSTRUMENTS") (field (name "MPN") "OPA627AU"))
      (libsource (lib "eagle-import") (part "OPA627U"))
    )
    (comp (ref "LED1")
      (value "RED")
      (footprint "eagle-import:LED_SML1206")
      (libsource (lib "eagle-import") (part "LEDVWV1206"))
    )
    (comp (ref "LED2")
      (value "RED")
      (footprint "eagle-import:LED_SML1206")
      (fields (field (name "SPICEPREFIX") "D"))
      (libsource (lib "eagle-import") (part "LEDVWV1206"))
    )
    (comp (ref "LED3")
      (value "RED")
      (footprint "eagle-import:LED_SML1206")
      (libsource (lib "eagle-import") (part "LEDVWV1206"))
    )
    (comp (ref "LED4")
      (value "RED")
      (footprint "eagle-import:LED_SML1206")
      (libsource (lib "eagle-import") (part "LEDVWV1206"))
    )
    (comp (ref "LED5")
      (value "RED")
      (footprint "eagle-import:LED_SML1206")
      (libsource (lib "eagle-import") (part "LEDVWV1206"))
    )
    (comp (ref "LED6")
      (value "RED")
      (footprint "eagle-import:LED_SML1206")
      (libsource (lib "eagle-import") (part "LEDVWV1206"))
    )
    (comp (ref "LED7")
      (value "RED")
      (footprint "eagle-import:LED_SML1206")
      (libsource (lib "eagle-import") (part "LEDVWV1206"))
    )
    (comp (ref "LED8")
      (value "RED")
      (footprint "eagle-import:LED_SML1206")
      (libsource (lib "eagle-import") (part "LEDVWV1206"))
    )
    (comp (ref "Q1")
      (value "LSK689")
      (footprint "eagle-import:SOT-23-6")
      (libsource (lib "eagle-import") (part "LSK689"))
    )
    (comp (ref "Q2")
      (value "KSA992")
      (footprint "eagle-import:TRANSISTOR_TO92-ECB_P")
      (libsource (lib "eagle-import") (part "BJT_PNPKSA992"))
    )
    (comp (ref "Q3")
      (value "KSC1845")
      (footprint "eagle-import:TRANSISTOR_TO92-ECB_N")
      (libsource (lib "eagle-import") (part "BJT_NPNKSC1845"))
    )
    (comp (ref "Q4")
      (value "LSK489")
      (footprint "eagle-import:SOT-23-6")
      (libsource (lib "eagle-import") (part "LSK489SOP-6"))
    )
    (comp (ref "Q5")
      (value "LS3550")
      (footprint "eagle-import:SOT-23-6")
      (libsource (lib "eagle-import") (part "LS3550"))
    )
    (comp (ref "Q6")
      (value "LS3250")
      (footprint "eagle-import:SOT-23-6")
      (libsource (lib "eagle-import") (part "LS3250"))
    )
    (comp (ref "Q7")
      (value "LS3250")
      (footprint "eagle-import:SOT-23-6")
      (libsource (lib "eagle-import") (part "LS3250"))
    )
    (comp (ref "Q8")
      (value "LS3550")
      (footprint "eagle-import:SOT-23-6")
      (libsource (lib "eagle-import") (part "LS3550"))
    )
    (comp (ref "Q9")
      (value "KSC1845")
      (footprint "eagle-import:TRANSISTOR_TO92-ECB_N")
      (libsource (lib "eagle-import") (part "BJT_NPNKSC1845"))
    )
    (comp (ref "Q10")
      (value "KSA992")
      (footprint "eagle-import:TRANSISTOR_TO92-ECB_P")
      (libsource (lib "eagle-import") (part "BJT_PNPKSA992"))
    )
    (comp (ref "Q11")
      (value "KSA992")
      (footprint "eagle-import:TRANSISTOR_TO92-ECB_P")
      (libsource (lib "eagle-import") (part "BJT_PNPKSA992"))
    )
    (comp (ref "Q12")
      (value "KSC1845")
      (footprint "eagle-import:TRANSISTOR_TO92-ECB_N")
      (libsource (lib "eagle-import") (part "BJT_NPNKSC1845"))
    )
    (comp (ref "Q13")
      (value "KSC1845")
      (footprint "eagle-import:TRANSISTOR_TO92-ECB_N")
      (libsource (lib "eagle-import") (part "BJT_NPNKSC1845"))
    )
    (comp (ref "Q14")
      (value "KSA992")
      (footprint "eagle-import:TRANSISTOR_TO92-ECB_P")
      (libsource (lib "eagle-import") (part "BJT_PNPKSA992"))
    )
    (comp (ref "Q15")
      (value "KSC1845")
      (footprint "eagle-import:TRANSISTOR_TO92-ECB_N")
      (libsource (lib "eagle-import") (part "BJT_NPNKSC1845"))
    )
    (comp (ref "Q16")
      (value "KSA992")
      (footprint "eagle-import:TRANSISTOR_TO92-ECB_P")
      (libsource (lib "eagle-import") (part "BJT_PNPKSA992"))
    )
    (comp (ref "Q17")
      (value "KSC1845")
      (footprint "eagle-import:TRANSISTOR_TO92-ECB_N")
      (libsource (lib "eagle-import") (part "BJT_NPNKSC1845"))
    )
    (comp (ref "Q18")
      (value "KSA992")
      (footprint "eagle-import:TRANSISTOR_TO92-ECB_P")
      (libsource (lib "eagle-import") (part "BJT_PNPKSA992"))
    )
    (comp (ref "Q19")
      (value "KSA992")
      (footprint "eagle-import:TRANSISTOR_TO92-ECB_P")
      (libsource (lib "eagle-import") (part "BJT_PNPKSA992"))
    )
    (comp (ref "Q20")
      (value "KSC1845")
      (footprint "eagle-import:TRANSISTOR_TO92-ECB_N")
      (libsource (lib "eagle-import") (part "BJT_NPNKSC1845"))
    )
    (comp (ref "Q21")
      (value "KSC1845")
      (footprint "eagle-import:TRANSISTOR_TO92-ECB_N")
      (libsource (lib "eagle-import") (part "BJT_NPNKSC1845"))
    )
    (comp (ref "Q22")
      (value "KSA992")
      (footprint "eagle-import:TRANSISTOR_TO92-ECB_P")
      (libsource (lib "eagle-import") (part "BJT_PNPKSA992"))
    )
    (comp (ref "Q23")
      (value "KSC1845")
      (footprint "eagle-import:TRANSISTOR_TO92-ECB_N")
      (libsource (lib "eagle-import") (part "BJT_NPNKSC1845"))
    )
    (comp (ref "Q24")
      (value "KSA992")
      (footprint "eagle-import:TRANSISTOR_TO92-ECB_P")
      (libsource (lib "eagle-import") (part "BJT_PNPKSA992"))
    )
    (comp (ref "R1")
      (value "5k")
      (footprint "eagle-import:RTRIM3296W")
      (fields (field (name "SPICEPREFIX") "Z"))
      (libsource (lib "eagle-import") (part "R-TRIMM3296W"))
    )
    (comp (ref "R2")
      (value "10K")
      (footprint "eagle-import:MINI_MELF-0204W")
      (libsource (lib "eagle-import") (part "R-EU_MELF0204W"))
    )
    (comp (ref "R3")
      (value "10K")
      (footprint "eagle-import:MINI_MELF-0204W")
      (libsource (lib "eagle-import") (part "R-EU_MELF0204W"))
    )
    (comp (ref "R4")
      (value "10K")
      (footprint "eagle-import:MINI_MELF-0204W")
      (libsource (lib "eagle-import") (part "R-EU_MELF0204W"))
    )
    (comp (ref "R5")
      (value "250")
      (footprint "eagle-import:MINI_MELF-0204W")
      (libsource (lib "eagle-import") (part "R-EU_MELF0204W"))
    )
    (comp (ref "R6")
      (value "1K")
      (footprint "eagle-import:MINI_MELF-0204W")
      (libsource (lib "eagle-import") (part "R-EU_MELF0204W"))
    )
    (comp (ref "R7")
      (value "250")
      (footprint "eagle-import:MINI_MELF-0204W")
      (fields (field (name "SPICEPREFIX") "R"))
      (libsource (lib "eagle-import") (part "R-EU_MELF0204W"))
    )
    (comp (ref "R8")
      (value "1K")
      (footprint "eagle-import:MINI_MELF-0204W")
      (libsource (lib "eagle-import") (part "R-EU_MELF0204W"))
    )
    (comp (ref "R9")
      (value "1K")
      (footprint "eagle-import:MINI_MELF-0204W")
      (libsource (lib "eagle-import") (part "R-EU_MELF0204W"))
    )
    (comp (ref "R10")
      (value "1K")
      (footprint "eagle-import:MINI_MELF-0204W")
      (libsource (lib "eagle-import") (part "R-EU_MELF0204W"))
    )
    (comp (ref "R11")
      (value "2k")
      (footprint "eagle-import:MINI_MELF-0204W")
      (libsource (lib "eagle-import") (part "R-EU_MELF0204W"))
    )
    (comp (ref "R12")
      (value "250")
      (footprint "eagle-import:MINI_MELF-0204W")
      (libsource (lib "eagle-import") (part "R-EU_MELF0204W"))
    )
    (comp (ref "R13")
      (value "250")
      (footprint "eagle-import:MINI_MELF-0204W")
      (libsource (lib "eagle-import") (part "R-EU_MELF0204W"))
    )
    (comp (ref "R14")
      (value "10K")
      (footprint "eagle-import:MINI_MELF-0204W")
      (libsource (lib "eagle-import") (part "R-EU_MELF0204W"))
    )
    (comp (ref "R15")
      (value "10K")
      (footprint "eagle-import:MINI_MELF-0204W")
      (libsource (lib "eagle-import") (part "R-EU_MELF0204W"))
    )
    (comp (ref "R16")
      (value "10K")
      (footprint "eagle-import:MINI_MELF-0204W")
      (libsource (lib "eagle-import") (part "R-EU_MELF0204W"))
    )
    (comp (ref "R17")
      (value "10K")
      (footprint "eagle-import:MINI_MELF-0204W")
      (libsource (lib "eagle-import") (part "R-EU_MELF0204W"))
    )
    (comp (ref "R18")
      (value "250")
      (footprint "eagle-import:MINI_MELF-0204W")
      (libsource (lib "eagle-import") (part "R-EU_MELF0204W"))
    )
    (comp (ref "R19")
      (value "250")
      (footprint "eagle-import:MINI_MELF-0204W")
      (libsource (lib "eagle-import") (part "R-EU_MELF0204W"))
    )
    (comp (ref "R20")
      (value "2k")
      (footprint "eagle-import:MINI_MELF-0204W")
      (libsource (lib "eagle-import") (part "R-EU_MELF0204W"))
    )
    (comp (ref "R21")
      (value "10K")
      (footprint "eagle-import:MINI_MELF-0204W")
      (libsource (lib "eagle-import") (part "R-EU_MELF0204W"))
    )
    (comp (ref "R22")
      (value "20K")
      (footprint "eagle-import:MINI_MELF-0204W")
      (libsource (lib "eagle-import") (part "R-EU_MELF0204W"))
    )
    (comp (ref "R23")
      (value "250")
      (footprint "eagle-import:MINI_MELF-0204W")
      (libsource (lib "eagle-import") (part "R-EU_MELF0204W"))
    )
    (comp (ref "R24")
      (value "10")
      (footprint "eagle-import:MINI_MELF-0204W")
      (libsource (lib "eagle-import") (part "R-EU_MELF0204W"))
    )
    (comp (ref "R25")
      (value "10")
      (footprint "eagle-import:MINI_MELF-0204W")
      (libsource (lib "eagle-import") (part "R-EU_MELF0204W"))
    )
    (comp (ref "R26")
      (value "250")
      (footprint "eagle-import:MINI_MELF-0204W")
      (libsource (lib "eagle-import") (part "R-EU_MELF0204W"))
    )
    (comp (ref "R27")
      (value "300")
      (footprint "eagle-import:MINI_MELF-0204W")
      (libsource (lib "eagle-import") (part "R-EU_MELF0204W"))
    )
    (comp (ref "R28")
      (value "300")
      (footprint "eagle-import:MINI_MELF-0204W")
      (libsource (lib "eagle-import") (part "R-EU_MELF0204W"))
    )
    (comp (ref "R29")
      (value "10K")
      (footprint "eagle-import:MINI_MELF-0204W")
      (libsource (lib "eagle-import") (part "R-EU_MELF0204W"))
    )
    (comp (ref "R30")
      (value "10")
      (footprint "eagle-import:MINI_MELF-0204W")
      (libsource (lib "eagle-import") (part "R-EU_MELF0204W"))
    )
    (comp (ref "R31")
      (value "10")
      (footprint "eagle-import:MINI_MELF-0204W")
      (libsource (lib "eagle-import") (part "R-EU_MELF0204W"))
    )
    (comp (ref "R32")
      (value "300")
      (footprint "eagle-import:MINI_MELF-0204W")
      (libsource (lib "eagle-import") (part "R-EU_MELF0204W"))
    )
    (comp (ref "R33")
      (value "300")
      (footprint "eagle-import:MINI_MELF-0204W")
      (libsource (lib "eagle-import") (part "R-EU_MELF0204W"))
    )
    (comp (ref "R34")
      (value "10")
      (footprint "eagle-import:MINI_MELF-0204W")
      (libsource (lib "eagle-import") (part "R-EU_MELF0204W"))
    )
    (comp (ref "R35")
      (value "10")
      (footprint "eagle-import:MINI_MELF-0204W")
      (libsource (lib "eagle-import") (part "R-EU_MELF0204W"))
    )
    (comp (ref "R36")
      (value "10K")
      (footprint "eagle-import:MINI_MELF-0204W")
      (libsource (lib "eagle-import") (part "R-EU_MELF0204W"))
    )
    (comp (ref "R37")
      (value "20K")
      (footprint "eagle-import:MINI_MELF-0204W")
      (libsource (lib "eagle-import") (part "R-EU_MELF0204W"))
    )
    (comp (ref "R38")
      (value "250")
      (footprint "eagle-import:MINI_MELF-0204W")
      (libsource (lib "eagle-import") (part "R-EU_MELF0204W"))
    )
    (comp (ref "R39")
      (value "10")
      (footprint "eagle-import:MINI_MELF-0204W")
      (libsource (lib "eagle-import") (part "R-EU_MELF0204W"))
    )
    (comp (ref "R40")
      (value "10")
      (footprint "eagle-import:MINI_MELF-0204W")
      (libsource (lib "eagle-import") (part "R-EU_MELF0204W"))
    )
    (comp (ref "R41")
      (value "250")
      (footprint "eagle-import:MINI_MELF-0204W")
      (libsource (lib "eagle-import") (part "R-EU_MELF0204W"))
    )
    (comp (ref "R42")
      (value "300")
      (footprint "eagle-import:MINI_MELF-0204W")
      (libsource (lib "eagle-import") (part "R-EU_MELF0204W"))
    )
    (comp (ref "R43")
      (value "300")
      (footprint "eagle-import:MINI_MELF-0204W")
      (libsource (lib "eagle-import") (part "R-EU_MELF0204W"))
    )
    (comp (ref "R44")
      (value "10K")
      (footprint "eagle-import:MINI_MELF-0204W")
      (libsource (lib "eagle-import") (part "R-EU_MELF0204W"))
    )
    (comp (ref "R45")
      (value "10")
      (footprint "eagle-import:MINI_MELF-0204W")
      (libsource (lib "eagle-import") (part "R-EU_MELF0204W"))
    )
    (comp (ref "R46")
      (value "10")
      (footprint "eagle-import:MINI_MELF-0204W")
      (libsource (lib "eagle-import") (part "R-EU_MELF0204W"))
    )
    (comp (ref "R47")
      (value "300")
      (footprint "eagle-import:MINI_MELF-0204W")
      (libsource (lib "eagle-import") (part "R-EU_MELF0204W"))
    )
    (comp (ref "R48")
      (value "300")
      (footprint "eagle-import:MINI_MELF-0204W")
      (libsource (lib "eagle-import") (part "R-EU_MELF0204W"))
    )
    (comp (ref "R49")
      (value "10")
      (footprint "eagle-import:MINI_MELF-0204W")
      (libsource (lib "eagle-import") (part "R-EU_MELF0204W"))
    )
    (comp (ref "R50")
      (value "10")
      (footprint "eagle-import:MINI_MELF-0204W")
      (libsource (lib "eagle-import") (part "R-EU_MELF0204W"))
    )
    (comp (ref "S1")
      (value "VWV")
      (footprint "eagle-import:VWV")
      (libsource (lib "eagle-import") (part "VWV"))
    )
    (comp (ref "X1")
      (value "KK-156-3")
      (footprint "eagle-import:KK-156-3")
      (fields (field (name "MF") "MOLEX"))
      (libsource (lib "eagle-import") (part "KK-156-3"))
    )
    (comp (ref "X2")
      (value "KK-156-3")
      (footprint "eagle-import:KK-156-3")
      (fields (field (name "MF") "MOLEX"))
      (libsource (lib "eagle-import") (part "KK-156-3"))
    )
    (comp (ref "B1")
      (value "MOS_BRIDGE")
      (footprint "eagle-import:GBU4S")
      (libsource (lib "eagle-import") (part "GBU4"))
    )
    (comp (ref "B2")
      (value "MOS_BRIDGE")
      (footprint "eagle-import:GBU4S")
      (libsource (lib "eagle-import") (part "GBU4"))
    )
    (comp (ref "C37")
      (value "10000uF")
      (footprint "eagle-import:EB35D")
      (libsource (lib "eagle-import") (part "CPOL-EUE10-35"))
    )
    (comp (ref "C38")
      (value "10000uF")
      (footprint "eagle-import:EB35D")
      (libsource (lib "eagle-import") (part "CPOL-EUE10-35"))
    )
    (comp (ref "C39")
      (value "0.1uF")
      (footprint "eagle-import:C050-075X075")
      (libsource (lib "eagle-import") (part "C-EU050-075X075"))
    )
    (comp (ref "C40")
      (value "47uF")
      (footprint "eagle-import:C1206")
      (libsource (lib "eagle-import") (part "C-EUC1206"))
    )
    (comp (ref "C41")
      (value "47uF")
      (footprint "eagle-import:C1206")
      (libsource (lib "eagle-import") (part "C-EUC1206"))
    )
    (comp (ref "C42")
      (value "0.1uF")
      (footprint "eagle-import:C050-075X075")
      (libsource (lib "eagle-import") (part "C-EU050-075X075"))
    )
    (comp (ref "C43")
      (value "0.1uF")
      (footprint "eagle-import:C0805")
      (libsource (lib "eagle-import") (part "C-EUC0805"))
    )
    (comp (ref "C44")
      (value "0.1uF")
      (footprint "eagle-import:C0805")
      (libsource (lib "eagle-import") (part "C-EUC0805"))
    )
    (comp (ref "C45")
      (value "0.1uF")
      (footprint "eagle-import:C0805")
      (libsource (lib "eagle-import") (part "C-EUC0805"))
    )
    (comp (ref "C46")
      (value "0.1uF")
      (footprint "eagle-import:C0805")
      (libsource (lib "eagle-import") (part "C-EUC0805"))
    )
    (comp (ref "C47")
      (value "10uF")
      (footprint "eagle-import:C1206")
      (libsource (lib "eagle-import") (part "C-EUC1206"))
    )
    (comp (ref "C48")
      (value "10uF")
      (footprint "eagle-import:C1206")
      (libsource (lib "eagle-import") (part "C-EUC1206"))
    )
    (comp (ref "C49")
      (value "0.1uF")
      (footprint "eagle-import:C0805")
      (libsource (lib "eagle-import") (part "C-EUC0805"))
    )
    (comp (ref "C50")
      (value "0.1uF")
      (footprint "eagle-import:C0805")
      (libsource (lib "eagle-import") (part "C-EUC0805"))
    )
    (comp (ref "C51")
      (value "47p")
      (footprint "eagle-import:C0805")
      (libsource (lib "eagle-import") (part "C-EUC0805"))
    )
    (comp (ref "C52")
      (value "47p")
      (footprint "eagle-import:C0805")
      (libsource (lib "eagle-import") (part "C-EUC0805"))
    )
    (comp (ref "C53")
      (value "10uF")
      (footprint "eagle-import:C1206")
      (libsource (lib "eagle-import") (part "C-EUC1206"))
    )
    (comp (ref "C54")
      (value "10uF")
      (footprint "eagle-import:C1206")
      (libsource (lib "eagle-import") (part "C-EUC1206"))
    )
    (comp (ref "C55")
      (value "4.7uF")
      (footprint "eagle-import:C050-075X075")
      (libsource (lib "eagle-import") (part "C-EU050-075X075"))
    )
    (comp (ref "C56")
      (value "4.7uF")
      (footprint "eagle-import:C050-075X075")
      (libsource (lib "eagle-import") (part "C-EU050-075X075"))
    )
    (comp (ref "D13")
      (value "BZT55B10")
      (footprint "eagle-import:SOD80C")
      (libsource (lib "eagle-import") (part "DIODE-SOD80C"))
    )
    (comp (ref "D14")
      (value "BZT55B10")
      (footprint "eagle-import:SOD80C")
      (libsource (lib "eagle-import") (part "DIODE-SOD80C"))
    )
    (comp (ref "D15")
      (value "S1G")
      (footprint "eagle-import:DO214AA")
      (libsource (lib "eagle-import") (part "DIODE-DO214AA"))
    )
    (comp (ref "D16")
      (value "S1G")
      (footprint "eagle-import:DO214AA")
      (libsource (lib "eagle-import") (part "DIODE-DO214AA"))
    )
    (comp (ref "D17")
      (value "LT1236-10")
      (footprint "eagle-import:SO8")
      (libsource (lib "eagle-import") (part "LINEAR-TECHNOLOGY_LT1021-VSO-8"))
    )
    (comp (ref "D18")
      (value "LT1236-10")
      (footprint "eagle-import:SO8")
      (libsource (lib "eagle-import") (part "LINEAR-TECHNOLOGY_LT1021-VSO-8"))
    )
    (comp (ref "IC5")
      (value "OPA827")
      (footprint "eagle-import:SOIC8")
      (libsource (lib "eagle-import") (part "LT10S837C"))
    )
    (comp (ref "IC6")
      (value "OPA827")
      (footprint "eagle-import:SOIC8")
      (libsource (lib "eagle-import") (part "LT10S837C"))
    )
    (comp (ref "LED13")
      (value "RED")
      (footprint "eagle-import:LED_SML1206")
      (libsource (lib "eagle-import") (part "LEDVWV1206"))
    )
    (comp (ref "LED14")
      (value "RED")
      (footprint "eagle-import:LED_SML1206")
      (libsource (lib "eagle-import") (part "LEDVWV1206"))
    )
    (comp (ref "LED15")
      (value "RED")
      (footprint "eagle-import:LED_SML1206")
      (libsource (lib "eagle-import") (part "LEDVWV1206"))
    )
    (comp (ref "LED16")
      (value "RED")
      (footprint "eagle-import:LED_SML1206")
      (libsource (lib "eagle-import") (part "LEDVWV1206"))
    )
    (comp (ref "LED17")
      (value "RED")
      (footprint "eagle-import:LED_SML1206")
      (libsource (lib "eagle-import") (part "LEDVWV1206"))
    )
    (comp (ref "LED18")
      (value "RED")
      (footprint "eagle-import:LED_SML1206")
      (libsource (lib "eagle-import") (part "LEDVWV1206"))
    )
    (comp (ref "Q79")
      (value "KSC1845")
      (footprint "eagle-import:TRANSISTOR_TO92-ECB_N")
      (libsource (lib "eagle-import") (part "BJT_NPNKSC1845"))
    )
    (comp (ref "Q80")
      (value "KSA992")
      (footprint "eagle-import:TRANSISTOR_TO92-ECB_P")
      (libsource (lib "eagle-import") (part "BJT_PNPKSA992"))
    )
    (comp (ref "Q81")
      (value "KSA992")
      (footprint "eagle-import:TRANSISTOR_TO92-ECB_P")
      (libsource (lib "eagle-import") (part "BJT_PNPKSA992"))
    )
    (comp (ref "Q82")
      (value "KSC1845")
      (footprint "eagle-import:TRANSISTOR_TO92-ECB_N")
      (libsource (lib "eagle-import") (part "BJT_NPNKSC1845"))
    )
    (comp (ref "Q83")
      (value "KSA992")
      (footprint "eagle-import:TRANSISTOR_TO92-ECB_P")
      (libsource (lib "eagle-import") (part "BJT_PNPKSA992"))
    )
    (comp (ref "Q84")
      (value "KSC1845")
      (footprint "eagle-import:TRANSISTOR_TO92-ECB_N")
      (libsource (lib "eagle-import") (part "BJT_NPNKSC1845"))
    )
    (comp (ref "Q85")
      (value "KSA992")
      (footprint "eagle-import:TRANSISTOR_TO92-ECB_P")
      (libsource (lib "eagle-import") (part "BJT_PNPKSA992"))
    )
    (comp (ref "Q86")
      (value "KSC1845")
      (footprint "eagle-import:TRANSISTOR_TO92-ECB_N")
      (libsource (lib "eagle-import") (part "BJT_NPNKSC1845"))
    )
    (comp (ref "Q87")
      (value "KSC1845")
      (footprint "eagle-import:TRANSISTOR_TO92-ECB_N")
      (libsource (lib "eagle-import") (part "BJT_NPNKSC1845"))
    )
    (comp (ref "Q88")
      (value "KSA992")
      (footprint "eagle-import:TRANSISTOR_TO92-ECB_P")
      (libsource (lib "eagle-import") (part "BJT_PNPKSA992"))
    )
    (comp (ref "Q89")
      (value "MJL4281A")
      (footprint "eagle-import:TRANSISTOR_TO247_BCE_N")
      (libsource (lib "eagle-import") (part "BJT_NPNMJL4281"))
    )
    (comp (ref "Q90")
      (value "MJL4302A")
      (footprint "eagle-import:TRANSISTOR_TO247_BCE_P")
      (libsource (lib "eagle-import") (part "BJT_PNPMJL4302"))
    )
    (comp (ref "Q91")
      (value "DN2540")
      (footprint "eagle-import:TRANSISTOR_TO92-SGD_N")
      (libsource (lib "eagle-import") (part "DN2540"))
    )
    (comp (ref "Q92")
      (value "DN2540")
      (footprint "eagle-import:TRANSISTOR_TO92-SGD_N")
      (libsource (lib "eagle-import") (part "DN2540"))
    )
    (comp (ref "R115")
      (value "10k")
      (footprint "eagle-import:MINI_MELF-0204W")
      (libsource (lib "eagle-import") (part "R-EU_MELF0204W"))
    )
    (comp (ref "R116")
      (value "10k")
      (footprint "eagle-import:MINI_MELF-0204W")
      (libsource (lib "eagle-import") (part "R-EU_MELF0204W"))
    )
    (comp (ref "R117")
      (value "1k")
      (footprint "eagle-import:MINI_MELF-0204W")
      (libsource (lib "eagle-import") (part "R-EU_MELF0204W"))
    )
    (comp (ref "R118")
      (value "1k")
      (footprint "eagle-import:MINI_MELF-0204W")
      (libsource (lib "eagle-import") (part "R-EU_MELF0204W"))
    )
    (comp (ref "R119")
      (value "100")
      (footprint "eagle-import:MINI_MELF-0204W")
      (libsource (lib "eagle-import") (part "R-EU_MELF0204W"))
    )
    (comp (ref "R120")
      (value "10")
      (footprint "eagle-import:MINI_MELF-0204W")
      (libsource (lib "eagle-import") (part "R-EU_MELF0204W"))
    )
    (comp (ref "R121")
      (value "10")
      (footprint "eagle-import:MINI_MELF-0204W")
      (libsource (lib "eagle-import") (part "R-EU_MELF0204W"))
    )
    (comp (ref "R122")
      (value "100")
      (footprint "eagle-import:MINI_MELF-0204W")
      (libsource (lib "eagle-import") (part "R-EU_MELF0204W"))
    )
    (comp (ref "R123")
      (value "10")
      (footprint "eagle-import:MINI_MELF-0204W")
      (libsource (lib "eagle-import") (part "R-EU_MELF0204W"))
    )
    (comp (ref "R124")
      (value "10")
      (footprint "eagle-import:MINI_MELF-0204W")
      (libsource (lib "eagle-import") (part "R-EU_MELF0204W"))
    )
    (comp (ref "R125")
      (value "1k")
      (footprint "eagle-import:MINI_MELF-0204W")
      (libsource (lib "eagle-import") (part "R-EU_MELF0204W"))
    )
    (comp (ref "R126")
      (value "1k")
      (footprint "eagle-import:MINI_MELF-0204W")
      (libsource (lib "eagle-import") (part "R-EU_MELF0204W"))
    )
    (comp (ref "R127")
      (value "1.5k")
      (footprint "eagle-import:MINI_MELF-0204W")
      (libsource (lib "eagle-import") (part "R-EU_MELF0204W"))
    )
    (comp (ref "R128")
      (value "1.5k")
      (footprint "eagle-import:MINI_MELF-0204W")
      (libsource (lib "eagle-import") (part "R-EU_MELF0204W"))
    )
    (comp (ref "R129")
      (value "1.5k")
      (footprint "eagle-import:MINI_MELF-0204W")
      (libsource (lib "eagle-import") (part "R-EU_MELF0204W"))
    )
    (comp (ref "R130")
      (value "1.5k")
      (footprint "eagle-import:MINI_MELF-0204W")
      (libsource (lib "eagle-import") (part "R-EU_MELF0204W"))
    )
    (comp (ref "R131")
      (value "10k")
      (footprint "eagle-import:MINI_MELF-0204W")
      (libsource (lib "eagle-import") (part "R-EU_MELF0204W"))
    )
    (comp (ref "R132")
      (value "10k")
      (footprint "eagle-import:MINI_MELF-0204W")
      (libsource (lib "eagle-import") (part "R-EU_MELF0204W"))
    )
    (comp (ref "X3")
      (value "KK-156-2")
      (footprint "eagle-import:KK-156-2")
      (fields (field (name "MF") "MOLEX"))
      (libsource (lib "eagle-import") (part "KK-156-2"))
    )
    (comp (ref "X4")
      (value "KK-156-2")
      (footprint "eagle-import:KK-156-2")
      (fields (field (name "MF") "MOLEX"))
      (libsource (lib "eagle-import") (part "KK-156-2"))
    )
  )
  (nets
    (net (code "1") (name "BOUT+") (class "Default")
      (node (ref "R29") (pin "1") (pinfunction "1_1") (pintype "passive"))
      (node (ref "R30") (pin "1") (pinfunction "1_1") (pintype "passive"))
      (node (ref "R31") (pin "2") (pinfunction "2_2") (pintype "passive"))
      (node (ref "R34") (pin "1") (pinfunction "1_1") (pintype "passive"))
      (node (ref "R35") (pin "2") (pinfunction "2_2") (pintype "passive"))
      (node (ref "R51") (pin "2") (pinfunction "2_2") (pintype "passive"))
    )
    (net (code "2") (name "BOUT-") (class "Default")
      (node (ref "R44") (pin "1") (pinfunction "1_1") (pintype "passive"))
      (node (ref "R45") (pin "1") (pinfunction "1_1") (pintype "passive"))
      (node (ref "R46") (pin "2") (pinfunction "2_2") (pintype "passive"))
      (node (ref "R49") (pin "1") (pinfunction "1_1") (pintype "passive"))
      (node (ref "R50") (pin "2") (pinfunction "2_2") (pintype "passive"))
      (node (ref "R83") (pin "2") (pinfunction "2_2") (pintype "passive"))
    )
    (net (code "3") (name "GND") (class "Default")
      (node (ref "B1") (pin "-") (pinfunction "-_-") (pintype "passive"))
      (node (ref "B2") (pin "+") (pinfunction "+_+") (pintype "passive"))
      (node (ref "C1") (pin "-") (pinfunction "-_-") (pintype "passive"))
      (node (ref "C10") (pin "1") (pinfunction "1_1") (pintype "passive"))
      (node (ref "C11") (pin "2") (pinfunction "2_2") (pintype "passive"))
      (node (ref "C12") (pin "1") (pinfunction "1_1") (pintype "passive"))
      (node (ref "C14") (pin "1") (pinfunction "1_1") (pintype "passive"))
      (node (ref "C15") (pin "2") (pinfunction "2_2") (pintype "passive"))
      (node (ref "C17") (pin "2") (pinfunction "2_2") (pintype "passive"))
      (node (ref "C19") (pin "1") (pinfunction "1_1") (pintype "passive"))
      (node (ref "C2") (pin "+") (pinfunction "+_+") (pintype "passive"))
      (node (ref "C20") (pin "2") (pinfunction "2_2") (pintype "passive"))
      (node (ref "C22") (pin "1") (pinfunction "1_1") (pintype "passive"))
      (node (ref "C23") (pin "2") (pinfunction "2_2") (pintype "passive"))
      (node (ref "C24") (pin "1") (pinfunction "1_1") (pintype "passive"))
      (node (ref "C25") (pin "-") (pinfunction "-_-") (pintype "passive"))
      (node (ref "C26") (pin "+") (pinfunction "+_+") (pintype "passive"))
      (node (ref "C27") (pin "2") (pinfunction "2_2") (pintype "passive"))
      (node (ref "C29") (pin "1") (pinfunction "1_1") (pintype "passive"))
      (node (ref "C3") (pin "1") (pinfunction "1_1") (pintype "passive"))
      (node (ref "C30") (pin "2") (pinfunction "2_2") (pintype "passive"))
      (node (ref "C32") (pin "1") (pinfunction "1_1") (pintype "passive"))
      (node (ref "C33") (pin "2") (pinfunction "2_2") (pintype "passive"))
      (node (ref "C34") (pin "1") (pinfunction "1_1") (pintype "passive"))
      (node (ref "C35") (pin "-") (pinfunction "-_-") (pintype "passive"))
      (node (ref "C36") (pin "+") (pinfunction "+_+") (pintype "passive"))
      (node (ref "C37") (pin "-") (pinfunction "-_-") (pintype "passive"))
      (node (ref "C38") (pin "+") (pinfunction "+_+") (pintype "passive"))
      (node (ref "C39") (pin "1") (pinfunction "1_1") (pintype "passive"))
      (node (ref "C4") (pin "2") (pinfunction "2_2") (pintype "passive"))
      (node (ref "C42") (pin "2") (pinfunction "2_2") (pintype "passive"))
      (node (ref "C45") (pin "1") (pinfunction "1_1") (pintype "passive"))
      (node (ref "C46") (pin "2") (pinfunction "2_2") (pintype "passive"))
      (node (ref "C47") (pin "2") (pinfunction "2_2") (pintype "passive"))
      (node (ref "C48") (pin "1") (pinfunction "1_1") (pintype "passive"))
      (node (ref "C49") (pin "2") (pinfunction "2_2") (pintype "passive"))
      (node (ref "C5") (pin "-") (pinfunction "-_-") (pintype "passive"))
      (node (ref "C50") (pin "1") (pinfunction "1_1") (pintype "passive"))
      (node (ref "C55") (pin "1") (pinfunction "1_1") (pintype "passive"))
      (node (ref "C56") (pin "2") (pinfunction "2_2") (pintype "passive"))
      (node (ref "C6") (pin "+") (pinfunction "+_+") (pintype "passive"))
      (node (ref "C7") (pin "-") (pinfunction "-_-") (pintype "passive"))
      (node (ref "C8") (pin "+") (pinfunction "+_+") (pintype "passive"))
      (node (ref "C9") (pin "2") (pinfunction "2_2") (pintype "passive"))
      (node (ref "D17") (pin "4") (pinfunction "GND_4") (pintype "passive"))
      (node (ref "D18") (pin "6") (pinfunction "OUT_6") (pintype "passive"))
      (node (ref "IC1") (pin "3") (pinfunction "+IN_3") (pintype "input"))
      (node (ref "IC2") (pin "3") (pinfunction "+IN_3") (pintype "input"))
      (node (ref "IC5") (pin "7") (pinfunction "V+_7") (pintype "power_in"))
      (node (ref "IC6") (pin "4") (pinfunction "V-_4") (pintype "power_in"))
      (node (ref "LED13") (pin "C") (pinfunction "C_C") (pintype "passive"))
      (node (ref "LED14") (pin "A") (pinfunction "A_A") (pintype "passive"))
      (node (ref "LED17") (pin "C") (pinfunction "C_C") (pintype "passive"))
      (node (ref "LED18") (pin "A") (pinfunction "A_A") (pintype "passive"))
      (node (ref "Q85") (pin "C") (pinfunction "C_C") (pintype "passive"))
      (node (ref "Q86") (pin "C") (pinfunction "C_C") (pintype "passive"))
      (node (ref "R107") (pin "2") (pinfunction "2_2") (pintype "passive"))
      (node (ref "R108") (pin "1") (pinfunction "1_1") (pintype "passive"))
      (node (ref "R11") (pin "1") (pinfunction "1_1") (pintype "passive"))
      (node (ref "R111") (pin "1") (pinfunction "1_1") (pintype "passive"))
      (node (ref "R117") (pin "2") (pinfunction "2_2") (pintype "passive"))
      (node (ref "R118") (pin "1") (pinfunction "1_1") (pintype "passive"))
      (node (ref "R128") (pin "1") (pinfunction "1_1") (pintype "passive"))
      (node (ref "R129") (pin "2") (pinfunction "2_2") (pintype "passive"))
      (node (ref "R15") (pin "1") (pinfunction "1_1") (pintype "passive"))
      (node (ref "R16") (pin "2") (pinfunction "2_2") (pintype "passive"))
      (node (ref "R20") (pin "1") (pinfunction "1_1") (pintype "passive"))
      (node (ref "R52") (pin "1") (pinfunction "1_1") (pintype "passive"))
      (node (ref "R63") (pin "1") (pinfunction "1_1") (pintype "passive"))
      (node (ref "R75") (pin "2") (pinfunction "2_2") (pintype "passive"))
      (node (ref "R76") (pin "1") (pinfunction "1_1") (pintype "passive"))
      (node (ref "R79") (pin "1") (pinfunction "1_1") (pintype "passive"))
      (node (ref "R84") (pin "1") (pinfunction "1_1") (pintype "passive"))
      (node (ref "R95") (pin "1") (pinfunction "1_1") (pintype "passive"))
      (node (ref "X1") (pin "2") (pinfunction "S_2") (pintype "passive"))
      (node (ref "X2") (pin "2") (pinfunction "S_2") (pintype "passive"))
    )
    (net (code "4") (name "IN+") (class "Default")
      (node (ref "Q1") (pin "1") (pinfunction "G_1") (pintype "passive"))
      (node (ref "Q4") (pin "1") (pinfunction "G_1") (pintype "passive"))
      (node (ref "X1") (pin "1") (pinfunction "S_1") (pintype "passive"))
    )
    (net (code "5") (name "IN-") (class "Default")
      (node (ref "Q1") (pin "4") (pinfunction "G_4") (pintype "passive"))
      (node (ref "Q4") (pin "4") (pinfunction "G_4") (pintype "passive"))
      (node (ref "X1") (pin "3") (pinfunction "S_3") (pintype "passive"))
    )
    (net (code "6") (name "Net-(B1-AC1)") (class "Default")
      (node (ref "B1") (pin "AC2") (pinfunction "AC1_AC2") (pintype "passive"))
      (node (ref "X3") (pin "1") (pinfunction "S_1") (pintype "passive"))
    )
    (net (code "7") (name "Net-(B1-AC2)") (class "Default")
      (node (ref "B1") (pin "AC1") (pinfunction "AC2_AC1") (pintype "passive"))
      (node (ref "X3") (pin "2") (pinfunction "S_2") (pintype "passive"))
    )
    (net (code "8") (name "Net-(B1-Pad+)") (class "Default")
      (node (ref "B1") (pin "+") (pinfunction "+_+") (pintype "passive"))
      (node (ref "C37") (pin "+") (pinfunction "+_+") (pintype "passive"))
      (node (ref "C42") (pin "1") (pinfunction "1_1") (pintype "passive"))
      (node (ref "D15") (pin "C") (pinfunction "C_C") (pintype "passive"))
      (node (ref "LED15") (pin "A") (pinfunction "A_A") (pintype "passive"))
      (node (ref "Q87") (pin "C") (pinfunction "C_C") (pintype "passive"))
      (node (ref "Q89") (pin "C") (pinfunction "C_C") (pintype "passive"))
      (node (ref "R115") (pin "1") (pinfunction "1_1") (pintype "passive"))
      (node (ref "R119") (pin "1") (pinfunction "1_1") (pintype "passive"))
    )
    (net (code "9") (name "Net-(B2-AC1)") (class "Default")
      (node (ref "B2") (pin "AC2") (pinfunction "AC1_AC2") (pintype "passive"))
      (node (ref "X4") (pin "2") (pinfunction "S_2") (pintype "passive"))
    )
    (net (code "10") (name "Net-(B2-AC2)") (class "Default")
      (node (ref "B2") (pin "AC1") (pinfunction "AC2_AC1") (pintype "passive"))
      (node (ref "X4") (pin "1") (pinfunction "S_1") (pintype "passive"))
    )
    (net (code "11") (name "Net-(B2-Pad-)") (class "Default")
      (node (ref "B2") (pin "-") (pinfunction "-_-") (pintype "passive"))
      (node (ref "C38") (pin "-") (pinfunction "-_-") (pintype "passive"))
      (node (ref "C39") (pin "2") (pinfunction "2_2") (pintype "passive"))
      (node (ref "D16") (pin "A") (pinfunction "A_A") (pintype "passive"))
      (node (ref "LED16") (pin "C") (pinfunction "C_C") (pintype "passive"))
      (node (ref "Q88") (pin "C") (pinfunction "C_C") (pintype "passive"))
      (node (ref "Q90") (pin "C") (pinfunction "C_C") (pintype "passive"))
      (node (ref "R116") (pin "2") (pinfunction "2_2") (pintype "passive"))
      (node (ref "R122") (pin "2") (pinfunction "2_2") (pintype "passive"))
    )
    (net (code "12") (name "Net-(C17-Pad1)") (class "Default")
      (node (ref "C17") (pin "1") (pinfunction "1_1") (pintype "passive"))
      (node (ref "Q26") (pin "B") (pinfunction "B_B") (pintype "passive"))
      (node (ref "Q27") (pin "B") (pinfunction "B_B") (pintype "passive"))
      (node (ref "R51") (pin "1") (pinfunction "1_1") (pintype "passive"))
      (node (ref "R52") (pin "2") (pinfunction "2_2") (pintype "passive"))
    )
    (net (code "13") (name "Net-(C18-Pad1)") (class "Default")
      (node (ref "C18") (pin "1") (pinfunction "1_1") (pintype "passive"))
      (node (ref "C19") (pin "2") (pinfunction "2_2") (pintype "passive"))
      (node (ref "Q39") (pin "C") (pinfunction "C_C") (pintype "passive"))
      (node (ref "Q43") (pin "C") (pinfunction "C_C") (pintype "passive"))
      (node (ref "Q45") (pin "C") (pinfunction "C_C") (pintype "passive"))
      (node (ref "Q46") (pin "B") (pinfunction "B_B") (pintype "passive"))
      (node (ref "R73") (pin "2") (pinfunction "2_2") (pintype "passive"))
      (node (ref "R75") (pin "1") (pinfunction "1_1") (pintype "passive"))
    )
    (net (code "14") (name "Net-(C27-Pad1)") (class "Default")
      (node (ref "C27") (pin "1") (pinfunction "1_1") (pintype "passive"))
      (node (ref "Q53") (pin "B") (pinfunction "B_B") (pintype "passive"))
      (node (ref "Q54") (pin "B") (pinfunction "B_B") (pintype "passive"))
      (node (ref "R83") (pin "1") (pinfunction "1_1") (pintype "passive"))
      (node (ref "R84") (pin "2") (pinfunction "2_2") (pintype "passive"))
    )
    (net (code "15") (name "Net-(C28-Pad1)") (class "Default")
      (node (ref "C28") (pin "1") (pinfunction "1_1") (pintype "passive"))
      (node (ref "C29") (pin "2") (pinfunction "2_2") (pintype "passive"))
      (node (ref "Q66") (pin "C") (pinfunction "C_C") (pintype "passive"))
      (node (ref "Q70") (pin "C") (pinfunction "C_C") (pintype "passive"))
      (node (ref "Q72") (pin "C") (pinfunction "C_C") (pintype "passive"))
      (node (ref "Q73") (pin "B") (pinfunction "B_B") (pintype "passive"))
      (node (ref "R105") (pin "2") (pinfunction "2_2") (pintype "passive"))
      (node (ref "R107") (pin "1") (pinfunction "1_1") (pintype "passive"))
    )
    (net (code "16") (name "Net-(C40-Pad1)") (class "Default")
      (node (ref "C40") (pin "1") (pinfunction "1_1") (pintype "passive"))
      (node (ref "C43") (pin "1") (pinfunction "1_1") (pintype "passive"))
      (node (ref "D13") (pin "C") (pinfunction "C_C") (pintype "passive"))
      (node (ref "Q83") (pin "C") (pinfunction "C_C") (pintype "passive"))
      (node (ref "Q87") (pin "B") (pinfunction "B_B") (pintype "passive"))
    )
    (net (code "17") (name "Net-(C40-Pad2)") (class "Default")
      (node (ref "C40") (pin "2") (pinfunction "2_2") (pintype "passive"))
      (node (ref "C43") (pin "2") (pinfunction "2_2") (pintype "passive"))
      (node (ref "D13") (pin "A") (pinfunction "A_A") (pintype "passive"))
      (node (ref "R120") (pin "1") (pinfunction "1_1") (pintype "passive"))
    )
    (net (code "18") (name "Net-(C41-Pad1)") (class "Default")
      (node (ref "C41") (pin "1") (pinfunction "1_1") (pintype "passive"))
      (node (ref "C44") (pin "1") (pinfunction "1_1") (pintype "passive"))
      (node (ref "D14") (pin "C") (pinfunction "C_C") (pintype "passive"))
      (node (ref "R121") (pin "2") (pinfunction "2_2") (pintype "passive"))
    )
    (net (code "19") (name "Net-(C41-Pad2)") (class "Default")
      (node (ref "C41") (pin "2") (pinfunction "2_2") (pintype "passive"))
      (node (ref "C44") (pin "2") (pinfunction "2_2") (pintype "passive"))
      (node (ref "D14") (pin "A") (pinfunction "A_A") (pintype "passive"))
      (node (ref "Q84") (pin "C") (pinfunction "C_C") (pintype "passive"))
      (node (ref "Q88") (pin "B") (pinfunction "B_B") (pintype "passive"))
    )
    (net (code "20") (name "Net-(D1-PadC)") (class "Default")
      (node (ref "D1") (pin "C") (pinfunction "C_C") (pintype "passive"))
      (node (ref "D2") (pin "A") (pinfunction "A_A") (pintype "passive"))
    )
    (net (code "21") (name "Net-(D2-PadC)") (class "Default")
      (node (ref "D2") (pin "C") (pinfunction "C_C") (pintype "passive"))
      (node (ref "Q25") (pin "B") (pinfunction "B_B") (pintype "passive"))
      (node (ref "R53") (pin "2") (pinfunction "2_2") (pintype "passive"))
    )
    (net (code "22") (name "Net-(D3-PadA)") (class "Default")
      (node (ref "D3") (pin "A") (pinfunction "A_A") (pintype "passive"))
      (node (ref "Q28") (pin "B") (pinfunction "B_B") (pintype "passive"))
      (node (ref "R53") (pin "1") (pinfunction "1_1") (pintype "passive"))
    )
    (net (code "23") (name "Net-(D3-PadC)") (class "Default")
      (node (ref "D3") (pin "C") (pinfunction "C_C") (pintype "passive"))
      (node (ref "D4") (pin "A") (pinfunction "A_A") (pintype "passive"))
    )
    (net (code "24") (name "Net-(D5-PadA)") (class "Default")
      (node (ref "D5") (pin "A") (pinfunction "A_A") (pintype "passive"))
      (node (ref "Q25") (pin "C") (pinfunction "C_C") (pintype "passive"))
      (node (ref "Q29") (pin "B") (pinfunction "B_B") (pintype "passive"))
    )
    (net (code "25") (name "Net-(D5-PadC)") (class "Default")
      (node (ref "D5") (pin "C") (pinfunction "C_C") (pintype "passive"))
      (node (ref "Q30") (pin "B") (pinfunction "B_B") (pintype "passive"))
      (node (ref "R55") (pin "2") (pinfunction "2_2") (pintype "passive"))
    )
    (net (code "26") (name "Net-(D6-PadA)") (class "Default")
      (node (ref "D6") (pin "A") (pinfunction "A_A") (pintype "passive"))
      (node (ref "Q31") (pin "B") (pinfunction "B_B") (pintype "passive"))
      (node (ref "R56") (pin "1") (pinfunction "1_1") (pintype "passive"))
    )
    (net (code "27") (name "Net-(D6-PadC)") (class "Default")
      (node (ref "D6") (pin "C") (pinfunction "C_C") (pintype "passive"))
      (node (ref "Q28") (pin "C") (pinfunction "C_C") (pintype "passive"))
      (node (ref "Q32") (pin "B") (pinfunction "B_B") (pintype "passive"))
    )
    (net (code "28") (name "Net-(D7-PadC)") (class "Default")
      (node (ref "D7") (pin "C") (pinfunction "C_C") (pintype "passive"))
      (node (ref "D8") (pin "A") (pinfunction "A_A") (pintype "passive"))
    )
    (net (code "29") (name "Net-(D8-PadC)") (class "Default")
      (node (ref "D8") (pin "C") (pinfunction "C_C") (pintype "passive"))
      (node (ref "Q52") (pin "B") (pinfunction "B_B") (pintype "passive"))
      (node (ref "R85") (pin "2") (pinfunction "2_2") (pintype "passive"))
    )
    (net (code "30") (name "Net-(D9-PadA)") (class "Default")
      (node (ref "D9") (pin "A") (pinfunction "A_A") (pintype "passive"))
      (node (ref "Q55") (pin "B") (pinfunction "B_B") (pintype "passive"))
      (node (ref "R85") (pin "1") (pinfunction "1_1") (pintype "passive"))
    )
    (net (code "31") (name "Net-(D10-PadA)") (class "Default")
      (node (ref "D10") (pin "A") (pinfunction "A_A") (pintype "passive"))
      (node (ref "D9") (pin "C") (pinfunction "C_C") (pintype "passive"))
    )
    (net (code "32") (name "Net-(D11-PadA)") (class "Default")
      (node (ref "D11") (pin "A") (pinfunction "A_A") (pintype "passive"))
      (node (ref "Q52") (pin "C") (pinfunction "C_C") (pintype "passive"))
      (node (ref "Q56") (pin "B") (pinfunction "B_B") (pintype "passive"))
    )
    (net (code "33") (name "Net-(D11-PadC)") (class "Default")
      (node (ref "D11") (pin "C") (pinfunction "C_C") (pintype "passive"))
      (node (ref "Q57") (pin "B") (pinfunction "B_B") (pintype "passive"))
      (node (ref "R87") (pin "2") (pinfunction "2_2") (pintype "passive"))
    )
    (net (code "34") (name "Net-(D12-PadA)") (class "Default")
      (node (ref "D12") (pin "A") (pinfunction "A_A") (pintype "passive"))
      (node (ref "Q58") (pin "B") (pinfunction "B_B") (pintype "passive"))
      (node (ref "R88") (pin "1") (pinfunction "1_1") (pintype "passive"))
    )
    (net (code "35") (name "Net-(D12-PadC)") (class "Default")
      (node (ref "D12") (pin "C") (pinfunction "C_C") (pintype "passive"))
      (node (ref "Q55") (pin "C") (pinfunction "C_C") (pintype "passive"))
      (node (ref "Q59") (pin "B") (pinfunction "B_B") (pintype "passive"))
    )
    (net (code "36") (name "Net-(D17-OUT)") (class "Default")
      (node (ref "C47") (pin "1") (pinfunction "1_1") (pintype "passive"))
      (node (ref "C49") (pin "1") (pinfunction "1_1") (pintype "passive"))
      (node (ref "D17") (pin "6") (pinfunction "OUT_6") (pintype "passive"))
      (node (ref "IC6") (pin "3") (pinfunction "+IN_3") (pintype "input"))
      (node (ref "Q91") (pin "G") (pinfunction "G_G") (pintype "passive"))
      (node (ref "R125") (pin "1") (pinfunction "1_1") (pintype "passive"))
    )
    (net (code "37") (name "Net-(D18-GND)") (class "Default")
      (node (ref "C48") (pin "2") (pinfunction "2_2") (pintype "passive"))
      (node (ref "C50") (pin "2") (pinfunction "2_2") (pintype "passive"))
      (node (ref "D18") (pin "4") (pinfunction "GND_4") (pintype "passive"))
      (node (ref "IC5") (pin "3") (pinfunction "+IN_3") (pintype "input"))
      (node (ref "Q92") (pin "D") (pinfunction "D_D") (pintype "passive"))
    )
    (net (code "38") (name "Net-(IC1--IN)") (class "Default")
      (node (ref "C13") (pin "2") (pinfunction "2_2") (pintype "passive"))
      (node (ref "IC1") (pin "2") (pinfunction "-IN_2") (pintype "input"))
      (node (ref "R29") (pin "2") (pinfunction "2_2") (pintype "passive"))
    )
    (net (code "39") (name "Net-(IC1-OUT)") (class "Default")
      (node (ref "C13") (pin "1") (pinfunction "1_1") (pintype "passive"))
      (node (ref "IC1") (pin "6") (pinfunction "OUT_6") (pintype "output"))
      (node (ref "R21") (pin "1") (pinfunction "1_1") (pintype "passive"))
    )
    (net (code "40") (name "Net-(IC2--IN)") (class "Default")
      (node (ref "C16") (pin "2") (pinfunction "2_2") (pintype "passive"))
      (node (ref "IC2") (pin "2") (pinfunction "-IN_2") (pintype "input"))
      (node (ref "R44") (pin "2") (pinfunction "2_2") (pintype "passive"))
    )
    (net (code "41") (name "Net-(IC2-OUT)") (class "Default")
      (node (ref "C16") (pin "1") (pinfunction "1_1") (pintype "passive"))
      (node (ref "IC2") (pin "6") (pinfunction "OUT_6") (pintype "output"))
      (node (ref "R36") (pin "1") (pinfunction "1_1") (pintype "passive"))
    )
    (net (code "42") (name "Net-(IC3-+IN)") (class "Default")
      (node (ref "C22") (pin "2") (pinfunction "2_2") (pintype "passive"))
      (node (ref "IC3") (pin "3") (pinfunction "+IN_3") (pintype "input"))
      (node (ref "R82") (pin "2") (pinfunction "2_2") (pintype "passive"))
    )
    (net (code "43") (name "Net-(IC3--IN)") (class "Default")
      (node (ref "C21") (pin "2") (pinfunction "2_2") (pintype "passive"))
      (node (ref "IC3") (pin "2") (pinfunction "-IN_2") (pintype "input"))
      (node (ref "R79") (pin "2") (pinfunction "2_2") (pintype "passive"))
    )
    (net (code "44") (name "Net-(IC3-OUT)") (class "Default")
      (node (ref "C21") (pin "1") (pinfunction "1_1") (pintype "passive"))
      (node (ref "IC3") (pin "6") (pinfunction "OUT_6") (pintype "output"))
      (node (ref "R68") (pin "1") (pinfunction "1_1") (pintype "passive"))
      (node (ref "R69") (pin "2") (pinfunction "2_2") (pintype "passive"))
    )
    (net (code "45") (name "Net-(IC4-+IN)") (class "Default")
      (node (ref "C32") (pin "2") (pinfunction "2_2") (pintype "passive"))
      (node (ref "IC4") (pin "3") (pinfunction "+IN_3") (pintype "input"))
      (node (ref "R114") (pin "2") (pinfunction "2_2") (pintype "passive"))
    )
    (net (code "46") (name "Net-(IC4--IN)") (class "Default")
      (node (ref "C31") (pin "2") (pinfunction "2_2") (pintype "passive"))
      (node (ref "IC4") (pin "2") (pinfunction "-IN_2") (pintype "input"))
      (node (ref "R111") (pin "2") (pinfunction "2_2") (pintype "passive"))
    )
    (net (code "47") (name "Net-(IC4-OUT)") (class "Default")
      (node (ref "C31") (pin "1") (pinfunction "1_1") (pintype "passive"))
      (node (ref "IC4") (pin "6") (pinfunction "OUT_6") (pintype "output"))
      (node (ref "R100") (pin "1") (pinfunction "1_1") (pintype "passive"))
      (node (ref "R101") (pin "2") (pinfunction "2_2") (pintype "passive"))
    )
    (net (code "48") (name "Net-(IC5--IN)") (class "Default")
      (node (ref "C52") (pin "2") (pinfunction "2_2") (pintype "passive"))
      (node (ref "C54") (pin "1") (pinfunction "1_1") (pintype "passive"))
      (node (ref "IC5") (pin "2") (pinfunction "-IN_2") (pintype "input"))
      (node (ref "R129") (pin "1") (pinfunction "1_1") (pintype "passive"))
      (node (ref "R130") (pin "2") (pinfunction "2_2") (pintype "passive"))
    )
    (net (code "49") (name "Net-(IC5-OUT)") (class "Default")
      (node (ref "C52") (pin "1") (pinfunction "1_1") (pintype "passive"))
      (node (ref "IC5") (pin "6") (pinfunction "OUT_6") (pintype "output"))
      (node (ref "R124") (pin "1") (pinfunction "1_1") (pintype "passive"))
    )
    (net (code "50") (name "Net-(IC6--IN)") (class "Default")
      (node (ref "C51") (pin "2") (pinfunction "2_2") (pintype "passive"))
      (node (ref "C53") (pin "2") (pinfunction "2_2") (pintype "passive"))
      (node (ref "IC6") (pin "2") (pinfunction "-IN_2") (pintype "input"))
      (node (ref "R127") (pin "1") (pinfunction "1_1") (pintype "passive"))
      (node (ref "R128") (pin "2") (pinfunction "2_2") (pintype "passive"))
    )
    (net (code "51") (name "Net-(IC6-OUT)") (class "Default")
      (node (ref "C51") (pin "1") (pinfunction "1_1") (pintype "passive"))
      (node (ref "IC6") (pin "6") (pinfunction "OUT_6") (pintype "output"))
      (node (ref "R123") (pin "1") (pinfunction "1_1") (pintype "passive"))
    )
    (net (code "52") (name "Net-(LED1-PadC)") (class "Default")
      (node (ref "LED1") (pin "C") (pinfunction "C_C") (pintype "passive"))
      (node (ref "Q2") (pin "B") (pinfunction "B_B") (pintype "passive"))
      (node (ref "R3") (pin "2") (pinfunction "2_2") (pintype "passive"))
    )
    (net (code "53") (name "Net-(LED2-PadA)") (class "Default")
      (node (ref "LED2") (pin "A") (pinfunction "A_A") (pintype "passive"))
      (node (ref "Q3") (pin "B") (pinfunction "B_B") (pintype "passive"))
      (node (ref "R4") (pin "1") (pinfunction "1_1") (pintype "passive"))
    )
    (net (code "54") (name "Net-(LED5-PadC)") (class "Default")
      (node (ref "LED5") (pin "C") (pinfunction "C_C") (pintype "passive"))
      (node (ref "Q11") (pin "B") (pinfunction "B_B") (pintype "passive"))
      (node (ref "R22") (pin "2") (pinfunction "2_2") (pintype "passive"))
    )
    (net (code "55") (name "Net-(LED6-PadA)") (class "Default")
      (node (ref "LED6") (pin "A") (pinfunction "A_A") (pintype "passive"))
      (node (ref "Q12") (pin "B") (pinfunction "B_B") (pintype "passive"))
      (node (ref "R22") (pin "1") (pinfunction "1_1") (pintype "passive"))
    )
    (net (code "56") (name "Net-(LED7-PadC)") (class "Default")
      (node (ref "LED7") (pin "C") (pinfunction "C_C") (pintype "passive"))
      (node (ref "Q19") (pin "B") (pinfunction "B_B") (pintype "passive"))
      (node (ref "R37") (pin "2") (pinfunction "2_2") (pintype "passive"))
    )
    (net (code "57") (name "Net-(LED8-PadA)") (class "Default")
      (node (ref "LED8") (pin "A") (pinfunction "A_A") (pintype "passive"))
      (node (ref "Q20") (pin "B") (pinfunction "B_B") (pintype "passive"))
      (node (ref "R37") (pin "1") (pinfunction "1_1") (pintype "passive"))
    )
    (net (code "58") (name "Net-(LED9-PadA)") (class "Default")
      (node (ref "LED9") (pin "A") (pinfunction "A_A") (pintype "passive"))
      (node (ref "Q35") (pin "E") (pinfunction "E_E") (pintype "passive"))
      (node (ref "R62") (pin "1") (pinfunction "1_1") (pintype "passive"))
    )
    (net (code "59") (name "Net-(LED9-PadC)") (class "Default")
      (node (ref "LED9") (pin "C") (pinfunction "C_C") (pintype "passive"))
      (node (ref "Q39") (pin "B") (pinfunction "B_B") (pintype "passive"))
      (node (ref "R65") (pin "2") (pinfunction "2_2") (pintype "passive"))
    )
    (net (code "60") (name "Net-(LED10-PadA)") (class "Default")
      (node (ref "LED10") (pin "A") (pinfunction "A_A") (pintype "passive"))
      (node (ref "Q40") (pin "B") (pinfunction "B_B") (pintype "passive"))
      (node (ref "R65") (pin "1") (pinfunction "1_1") (pintype "passive"))
    )
    (net (code "61") (name "Net-(LED10-PadC)") (class "Default")
      (node (ref "LED10") (pin "C") (pinfunction "C_C") (pintype "passive"))
      (node (ref "Q38") (pin "E") (pinfunction "E_E") (pintype "passive"))
      (node (ref "R64") (pin "2") (pinfunction "2_2") (pintype "passive"))
    )
    (net (code "62") (name "Net-(LED11-PadA)") (class "Default")
      (node (ref "LED11") (pin "A") (pinfunction "A_A") (pintype "passive"))
      (node (ref "Q62") (pin "E") (pinfunction "E_E") (pintype "passive"))
      (node (ref "R94") (pin "1") (pinfunction "1_1") (pintype "passive"))
    )
    (net (code "63") (name "Net-(LED11-PadC)") (class "Default")
      (node (ref "LED11") (pin "C") (pinfunction "C_C") (pintype "passive"))
      (node (ref "Q66") (pin "B") (pinfunction "B_B") (pintype "passive"))
      (node (ref "R97") (pin "2") (pinfunction "2_2") (pintype "passive"))
    )
    (net (code "64") (name "Net-(LED12-PadA)") (class "Default")
      (node (ref "LED12") (pin "A") (pinfunction "A_A") (pintype "passive"))
      (node (ref "Q67") (pin "B") (pinfunction "B_B") (pintype "passive"))
      (node (ref "R97") (pin "1") (pinfunction "1_1") (pintype "passive"))
    )
    (net (code "65") (name "Net-(LED12-PadC)") (class "Default")
      (node (ref "LED12") (pin "C") (pinfunction "C_C") (pintype "passive"))
      (node (ref "Q65") (pin "E") (pinfunction "E_E") (pintype "passive"))
      (node (ref "R96") (pin "2") (pinfunction "2_2") (pintype "passive"))
    )
    (net (code "66") (name "Net-(LED13-PadA)") (class "Default")
      (node (ref "LED13") (pin "A") (pinfunction "A_A") (pintype "passive"))
      (node (ref "Q79") (pin "B") (pinfunction "B_B") (pintype "passive"))
      (node (ref "R115") (pin "2") (pinfunction "2_2") (pintype "passive"))
    )
    (net (code "67") (name "Net-(LED14-PadC)") (class "Default")
      (node (ref "LED14") (pin "C") (pinfunction "C_C") (pintype "passive"))
      (node (ref "Q80") (pin "B") (pinfunction "B_B") (pintype "passive"))
      (node (ref "R116") (pin "1") (pinfunction "1_1") (pintype "passive"))
    )
    (net (code "68") (name "Net-(LED15-PadC)") (class "Default")
      (node (ref "LED15") (pin "C") (pinfunction "C_C") (pintype "passive"))
      (node (ref "Q81") (pin "E") (pinfunction "E_E") (pintype "passive"))
    )
    (net (code "69") (name "Net-(LED16-PadA)") (class "Default")
      (node (ref "LED16") (pin "A") (pinfunction "A_A") (pintype "passive"))
      (node (ref "Q82") (pin "E") (pinfunction "E_E") (pintype "passive"))
    )
    (net (code "70") (name "Net-(LED17-PadA)") (class "Default")
      (node (ref "LED17") (pin "A") (pinfunction "A_A") (pintype "passive"))
      (node (ref "R131") (pin "1") (pinfunction "1_1") (pintype "passive"))
    )
    (net (code "71") (name "Net-(LED18-PadC)") (class "Default")
      (node (ref "LED18") (pin "C") (pinfunction "C_C") (pintype "passive"))
      (node (ref "R132") (pin "2") (pinfunction "2_2") (pintype "passive"))
    )
    (net (code "72") (name "Net-(Q1A-D)") (class "Default")
      (node (ref "Q1") (pin "2") (pinfunction "D_2") (pintype "passive"))
      (node (ref "Q6") (pin "5") (pinfunction "E_5") (pintype "passive"))
      (node (ref "Q7") (pin "6") (pinfunction "C_6") (pintype "passive"))
    )
    (net (code "73") (name "Net-(Q1A-S)") (class "Default")
      (node (ref "Q1") (pin "3") (pinfunction "S_3") (pintype "passive"))
      (node (ref "R6") (pin "1") (pinfunction "1_1") (pintype "passive"))
    )
    (net (code "74") (name "Net-(Q1B-D)") (class "Default")
      (node (ref "Q1") (pin "5") (pinfunction "D_5") (pintype "passive"))
      (node (ref "Q6") (pin "2") (pinfunction "E_2") (pintype "passive"))
      (node (ref "Q7") (pin "4") (pinfunction "C_4") (pintype "passive"))
    )
    (net (code "75") (name "Net-(Q1B-S)") (class "Default")
      (node (ref "Q1") (pin "6") (pinfunction "S_6") (pintype "passive"))
      (node (ref "R8") (pin "1") (pinfunction "1_1") (pintype "passive"))
    )
    (net (code "76") (name "Net-(Q2-PadC)") (class "Default")
      (node (ref "Q2") (pin "C") (pinfunction "C_C") (pintype "passive"))
      (node (ref "R6") (pin "2") (pinfunction "2_2") (pintype "passive"))
      (node (ref "R8") (pin "2") (pinfunction "2_2") (pintype "passive"))
    )
    (net (code "77") (name "Net-(Q2-PadE)") (class "Default")
      (node (ref "Q2") (pin "E") (pinfunction "E_E") (pintype "passive"))
      (node (ref "R5") (pin "1") (pinfunction "1_1") (pintype "passive"))
    )
    (net (code "78") (name "Net-(Q3-PadC)") (class "Default")
      (node (ref "Q3") (pin "C") (pinfunction "C_C") (pintype "passive"))
      (node (ref "R10") (pin "1") (pinfunction "1_1") (pintype "passive"))
      (node (ref "R9") (pin "1") (pinfunction "1_1") (pintype "passive"))
    )
    (net (code "79") (name "Net-(Q3-PadE)") (class "Default")
      (node (ref "Q3") (pin "E") (pinfunction "E_E") (pintype "passive"))
      (node (ref "R7") (pin "2") (pinfunction "2_2") (pintype "passive"))
    )
    (net (code "80") (name "Net-(Q4A-D)") (class "Default")
      (node (ref "Q4") (pin "2") (pinfunction "D_2") (pintype "passive"))
      (node (ref "Q5") (pin "5") (pinfunction "E_5") (pintype "passive"))
      (node (ref "Q8") (pin "4") (pinfunction "C_4") (pintype "passive"))
    )
    (net (code "81") (name "Net-(Q4A-S)") (class "Default")
      (node (ref "Q4") (pin "3") (pinfunction "S_3") (pintype "passive"))
      (node (ref "R9") (pin "2") (pinfunction "2_2") (pintype "passive"))
    )
    (net (code "82") (name "Net-(Q4B-D)") (class "Default")
      (node (ref "Q4") (pin "5") (pinfunction "D_5") (pintype "passive"))
      (node (ref "Q5") (pin "2") (pinfunction "E_2") (pintype "passive"))
      (node (ref "Q8") (pin "6") (pinfunction "C_6") (pintype "passive"))
    )
    (net (code "83") (name "Net-(Q4B-S)") (class "Default")
      (node (ref "Q4") (pin "6") (pinfunction "S_6") (pintype "passive"))
      (node (ref "R10") (pin "2") (pinfunction "2_2") (pintype "passive"))
    )
    (net (code "84") (name "Net-(Q5A-B)") (class "Default")
      (node (ref "Q5") (pin "1") (pinfunction "B_1") (pintype "passive"))
      (node (ref "Q5") (pin "3") (pinfunction "B_3") (pintype "passive"))
      (node (ref "R14") (pin "1") (pinfunction "1_1") (pintype "passive"))
      (node (ref "R15") (pin "2") (pinfunction "2_2") (pintype "passive"))
    )
    (net (code "85") (name "Net-(Q6A-B)") (class "Default")
      (node (ref "Q6") (pin "1") (pinfunction "B_1") (pintype "passive"))
      (node (ref "Q6") (pin "3") (pinfunction "B_3") (pintype "passive"))
      (node (ref "R16") (pin "1") (pinfunction "1_1") (pintype "passive"))
      (node (ref "R17") (pin "2") (pinfunction "2_2") (pintype "passive"))
    )
    (net (code "86") (name "Net-(Q7A-B)") (class "Default")
      (node (ref "LED4") (pin "A") (pinfunction "A_A") (pintype "passive"))
      (node (ref "Q7") (pin "1") (pinfunction "B_1") (pintype "passive"))
      (node (ref "Q7") (pin "3") (pinfunction "B_3") (pintype "passive"))
      (node (ref "R17") (pin "1") (pinfunction "1_1") (pintype "passive"))
    )
    (net (code "87") (name "Net-(Q7A-E)") (class "Default")
      (node (ref "Q7") (pin "5") (pinfunction "E_5") (pintype "passive"))
      (node (ref "R13") (pin "2") (pinfunction "2_2") (pintype "passive"))
    )
    (net (code "88") (name "Net-(Q7B-E)") (class "Default")
      (node (ref "Q7") (pin "2") (pinfunction "E_2") (pintype "passive"))
      (node (ref "R19") (pin "2") (pinfunction "2_2") (pintype "passive"))
    )
    (net (code "89") (name "Net-(Q8A-B)") (class "Default")
      (node (ref "LED3") (pin "C") (pinfunction "C_C") (pintype "passive"))
      (node (ref "Q8") (pin "1") (pinfunction "B_1") (pintype "passive"))
      (node (ref "Q8") (pin "3") (pinfunction "B_3") (pintype "passive"))
      (node (ref "R14") (pin "2") (pinfunction "2_2") (pintype "passive"))
    )
    (net (code "90") (name "Net-(Q8A-E)") (class "Default")
      (node (ref "Q8") (pin "5") (pinfunction "E_5") (pintype "passive"))
      (node (ref "R18") (pin "1") (pinfunction "1_1") (pintype "passive"))
    )
    (net (code "91") (name "Net-(Q8B-E)") (class "Default")
      (node (ref "Q8") (pin "2") (pinfunction "E_2") (pintype "passive"))
      (node (ref "R12") (pin "1") (pinfunction "1_1") (pintype "passive"))
    )
    (net (code "92") (name "Net-(Q9-PadE)") (class "Default")
      (node (ref "Q9") (pin "E") (pinfunction "E_E") (pintype "passive"))
      (node (ref "R25") (pin "1") (pinfunction "1_1") (pintype "passive"))
    )
    (net (code "93") (name "Net-(Q10-PadE)") (class "Default")
      (node (ref "Q10") (pin "E") (pinfunction "E_E") (pintype "passive"))
      (node (ref "R24") (pin "2") (pinfunction "2_2") (pintype "passive"))
    )
    (net (code "94") (name "Net-(Q11-PadC)") (class "Default")
      (node (ref "Q11") (pin "C") (pinfunction "C_C") (pintype "passive"))
      (node (ref "R24") (pin "1") (pinfunction "1_1") (pintype "passive"))
      (node (ref "R27") (pin "2") (pinfunction "2_2") (pintype "passive"))
      (node (ref "R32") (pin "2") (pinfunction "2_2") (pintype "passive"))
    )
    (net (code "95") (name "Net-(Q11-PadE)") (class "Default")
      (node (ref "Q11") (pin "E") (pinfunction "E_E") (pintype "passive"))
      (node (ref "R23") (pin "1") (pinfunction "1_1") (pintype "passive"))
    )
    (net (code "96") (name "Net-(Q12-PadC)") (class "Default")
      (node (ref "Q12") (pin "C") (pinfunction "C_C") (pintype "passive"))
      (node (ref "R25") (pin "2") (pinfunction "2_2") (pintype "passive"))
      (node (ref "R28") (pin "1") (pinfunction "1_1") (pintype "passive"))
      (node (ref "R33") (pin "1") (pinfunction "1_1") (pintype "passive"))
    )
    (net (code "97") (name "Net-(Q12-PadE)") (class "Default")
      (node (ref "Q12") (pin "E") (pinfunction "E_E") (pintype "passive"))
      (node (ref "R26") (pin "2") (pinfunction "2_2") (pintype "passive"))
    )
    (net (code "98") (name "Net-(Q13-PadB)") (class "Default")
      (node (ref "Q13") (pin "B") (pinfunction "B_B") (pintype "passive"))
      (node (ref "R27") (pin "1") (pinfunction "1_1") (pintype "passive"))
    )
    (net (code "99") (name "Net-(Q13-PadE)") (class "Default")
      (node (ref "Q13") (pin "E") (pinfunction "E_E") (pintype "passive"))
      (node (ref "R30") (pin "2") (pinfunction "2_2") (pintype "passive"))
    )
    (net (code "100") (name "Net-(Q14-PadB)") (class "Default")
      (node (ref "Q14") (pin "B") (pinfunction "B_B") (pintype "passive"))
      (node (ref "R28") (pin "2") (pinfunction "2_2") (pintype "passive"))
    )
    (net (code "101") (name "Net-(Q14-PadE)") (class "Default")
      (node (ref "Q14") (pin "E") (pinfunction "E_E") (pintype "passive"))
      (node (ref "R31") (pin "1") (pinfunction "1_1") (pintype "passive"))
    )
    (net (code "102") (name "Net-(Q15-PadB)") (class "Default")
      (node (ref "Q15") (pin "B") (pinfunction "B_B") (pintype "passive"))
      (node (ref "R32") (pin "1") (pinfunction "1_1") (pintype "passive"))
    )
    (net (code "103") (name "Net-(Q15-PadE)") (class "Default")
      (node (ref "Q15") (pin "E") (pinfunction "E_E") (pintype "passive"))
      (node (ref "R34") (pin "2") (pinfunction "2_2") (pintype "passive"))
    )
    (net (code "104") (name "Net-(Q16-PadB)") (class "Default")
      (node (ref "Q16") (pin "B") (pinfunction "B_B") (pintype "passive"))
      (node (ref "R33") (pin "2") (pinfunction "2_2") (pintype "passive"))
    )
    (net (code "105") (name "Net-(Q16-PadE)") (class "Default")
      (node (ref "Q16") (pin "E") (pinfunction "E_E") (pintype "passive"))
      (node (ref "R35") (pin "1") (pinfunction "1_1") (pintype "passive"))
    )
    (net (code "106") (name "Net-(Q17-PadE)") (class "Default")
      (node (ref "Q17") (pin "E") (pinfunction "E_E") (pintype "passive"))
      (node (ref "R40") (pin "1") (pinfunction "1_1") (pintype "passive"))
    )
    (net (code "107") (name "Net-(Q18-PadE)") (class "Default")
      (node (ref "Q18") (pin "E") (pinfunction "E_E") (pintype "passive"))
      (node (ref "R39") (pin "2") (pinfunction "2_2") (pintype "passive"))
    )
    (net (code "108") (name "Net-(Q19-PadC)") (class "Default")
      (node (ref "Q19") (pin "C") (pinfunction "C_C") (pintype "passive"))
      (node (ref "R39") (pin "1") (pinfunction "1_1") (pintype "passive"))
      (node (ref "R42") (pin "2") (pinfunction "2_2") (pintype "passive"))
      (node (ref "R47") (pin "2") (pinfunction "2_2") (pintype "passive"))
    )
    (net (code "109") (name "Net-(Q19-PadE)") (class "Default")
      (node (ref "Q19") (pin "E") (pinfunction "E_E") (pintype "passive"))
      (node (ref "R38") (pin "1") (pinfunction "1_1") (pintype "passive"))
    )
    (net (code "110") (name "Net-(Q20-PadC)") (class "Default")
      (node (ref "Q20") (pin "C") (pinfunction "C_C") (pintype "passive"))
      (node (ref "R40") (pin "2") (pinfunction "2_2") (pintype "passive"))
      (node (ref "R43") (pin "1") (pinfunction "1_1") (pintype "passive"))
      (node (ref "R48") (pin "1") (pinfunction "1_1") (pintype "passive"))
    )
    (net (code "111") (name "Net-(Q20-PadE)") (class "Default")
      (node (ref "Q20") (pin "E") (pinfunction "E_E") (pintype "passive"))
      (node (ref "R41") (pin "2") (pinfunction "2_2") (pintype "passive"))
    )
    (net (code "112") (name "Net-(Q21-PadB)") (class "Default")
      (node (ref "Q21") (pin "B") (pinfunction "B_B") (pintype "passive"))
      (node (ref "R42") (pin "1") (pinfunction "1_1") (pintype "passive"))
    )
    (net (code "113") (name "Net-(Q21-PadE)") (class "Default")
      (node (ref "Q21") (pin "E") (pinfunction "E_E") (pintype "passive"))
      (node (ref "R45") (pin "2") (pinfunction "2_2") (pintype "passive"))
    )
    (net (code "114") (name "Net-(Q22-PadB)") (class "Default")
      (node (ref "Q22") (pin "B") (pinfunction "B_B") (pintype "passive"))
      (node (ref "R43") (pin "2") (pinfunction "2_2") (pintype "passive"))
    )
    (net (code "115") (name "Net-(Q22-PadE)") (class "Default")
      (node (ref "Q22") (pin "E") (pinfunction "E_E") (pintype "passive"))
      (node (ref "R46") (pin "1") (pinfunction "1_1") (pintype "passive"))
    )
    (net (code "116") (name "Net-(Q23-PadB)") (class "Default")
      (node (ref "Q23") (pin "B") (pinfunction "B_B") (pintype "passive"))
      (node (ref "R47") (pin "1") (pinfunction "1_1") (pintype "passive"))
    )
    (net (code "117") (name "Net-(Q23-PadE)") (class "Default")
      (node (ref "Q23") (pin "E") (pinfunction "E_E") (pintype "passive"))
      (node (ref "R49") (pin "2") (pinfunction "2_2") (pintype "passive"))
    )
    (net (code "118") (name "Net-(Q24-PadB)") (class "Default")
      (node (ref "Q24") (pin "B") (pinfunction "B_B") (pintype "passive"))
      (node (ref "R48") (pin "2") (pinfunction "2_2") (pintype "passive"))
    )
    (net (code "119") (name "Net-(Q24-PadE)") (class "Default")
      (node (ref "Q24") (pin "E") (pinfunction "E_E") (pintype "passive"))
      (node (ref "R50") (pin "1") (pinfunction "1_1") (pintype "passive"))
    )
    (net (code "120") (name "Net-(Q25-PadE)") (class "Default")
      (node (ref "Q25") (pin "E") (pinfunction "E_E") (pintype "passive"))
      (node (ref "R54") (pin "1") (pinfunction "1_1") (pintype "passive"))
    )
    (net (code "121") (name "Net-(Q26-PadC)") (class "Default")
      (node (ref "Q26") (pin "C") (pinfunction "C_C") (pintype "passive"))
      (node (ref "Q31") (pin "E") (pinfunction "E_E") (pintype "passive"))
      (node (ref "R60") (pin "1") (pinfunction "1_1") (pintype "passive"))
    )
    (net (code "122") (name "Net-(Q26-PadE)") (class "Default")
      (node (ref "Q26") (pin "E") (pinfunction "E_E") (pintype "passive"))
      (node (ref "R55") (pin "1") (pinfunction "1_1") (pintype "passive"))
    )
    (net (code "123") (name "Net-(Q27-PadC)") (class "Default")
      (node (ref "Q27") (pin "C") (pinfunction "C_C") (pintype "passive"))
      (node (ref "Q30") (pin "E") (pinfunction "E_E") (pintype "passive"))
      (node (ref "R59") (pin "2") (pinfunction "2_2") (pintype "passive"))
    )
    (net (code "124") (name "Net-(Q27-PadE)") (class "Default")
      (node (ref "Q27") (pin "E") (pinfunction "E_E") (pintype "passive"))
      (node (ref "R56") (pin "2") (pinfunction "2_2") (pintype "passive"))
    )
    (net (code "125") (name "Net-(Q28-PadE)") (class "Default")
      (node (ref "Q28") (pin "E") (pinfunction "E_E") (pintype "passive"))
      (node (ref "R57") (pin "2") (pinfunction "2_2") (pintype "passive"))
    )
    (net (code "126") (name "Net-(Q29-PadC)") (class "Default")
      (node (ref "Q29") (pin "C") (pinfunction "C_C") (pintype "passive"))
      (node (ref "Q33") (pin "C") (pinfunction "C_C") (pintype "passive"))
      (node (ref "Q36") (pin "B") (pinfunction "B_B") (pintype "passive"))
    )
    (net (code "127") (name "Net-(Q29-PadE)") (class "Default")
      (node (ref "Q29") (pin "E") (pinfunction "E_E") (pintype "passive"))
      (node (ref "Q30") (pin "C") (pinfunction "C_C") (pintype "passive"))
    )
    (net (code "128") (name "Net-(Q31-PadC)") (class "Default")
      (node (ref "Q31") (pin "C") (pinfunction "C_C") (pintype "passive"))
      (node (ref "Q32") (pin "E") (pinfunction "E_E") (pintype "passive"))
    )
    (net (code "129") (name "Net-(Q32-PadC)") (class "Default")
      (node (ref "Q32") (pin "C") (pinfunction "C_C") (pintype "passive"))
      (node (ref "Q34") (pin "C") (pinfunction "C_C") (pintype "passive"))
      (node (ref "Q37") (pin "B") (pinfunction "B_B") (pintype "passive"))
    )
    (net (code "130") (name "Net-(Q33-PadB)") (class "Default")
      (node (ref "Q33") (pin "B") (pinfunction "B_B") (pintype "passive"))
      (node (ref "Q35") (pin "B") (pinfunction "B_B") (pintype "passive"))
      (node (ref "Q35") (pin "C") (pinfunction "C_C") (pintype "passive"))
      (node (ref "Q36") (pin "E") (pinfunction "E_E") (pintype "passive"))
    )
    (net (code "131") (name "Net-(Q33-PadE)") (class "Default")
      (node (ref "Q33") (pin "E") (pinfunction "E_E") (pintype "passive"))
      (node (ref "R58") (pin "1") (pinfunction "1_1") (pintype "passive"))
    )
    (net (code "132") (name "Net-(Q34-PadB)") (class "Default")
      (node (ref "Q34") (pin "B") (pinfunction "B_B") (pintype "passive"))
      (node (ref "Q37") (pin "E") (pinfunction "E_E") (pintype "passive"))
      (node (ref "Q38") (pin "B") (pinfunction "B_B") (pintype "passive"))
      (node (ref "Q38") (pin "C") (pinfunction "C_C") (pintype "passive"))
    )
    (net (code "133") (name "Net-(Q34-PadE)") (class "Default")
      (node (ref "Q34") (pin "E") (pinfunction "E_E") (pintype "passive"))
      (node (ref "R61") (pin "2") (pinfunction "2_2") (pintype "passive"))
    )
    (net (code "134") (name "Net-(Q36-PadC)") (class "Default")
      (node (ref "Q36") (pin "C") (pinfunction "C_C") (pintype "passive"))
      (node (ref "Q39") (pin "E") (pinfunction "E_E") (pintype "passive"))
    )
    (net (code "135") (name "Net-(Q37-PadC)") (class "Default")
      (node (ref "Q37") (pin "C") (pinfunction "C_C") (pintype "passive"))
      (node (ref "Q40") (pin "E") (pinfunction "E_E") (pintype "passive"))
    )
    (net (code "136") (name "Net-(Q41-PadB)") (class "Default")
      (node (ref "Q41") (pin "B") (pinfunction "B_B") (pintype "passive"))
      (node (ref "Q41") (pin "C") (pinfunction "C_C") (pintype "passive"))
      (node (ref "Q43") (pin "B") (pinfunction "B_B") (pintype "passive"))
      (node (ref "R68") (pin "2") (pinfunction "2_2") (pintype "passive"))
    )
    (net (code "137") (name "Net-(Q41-PadE)") (class "Default")
      (node (ref "Q41") (pin "E") (pinfunction "E_E") (pintype "passive"))
      (node (ref "R67") (pin "1") (pinfunction "1_1") (pintype "passive"))
    )
    (net (code "138") (name "Net-(Q42-PadB)") (class "Default")
      (node (ref "Q42") (pin "B") (pinfunction "B_B") (pintype "passive"))
      (node (ref "Q42") (pin "C") (pinfunction "C_C") (pintype "passive"))
      (node (ref "Q44") (pin "B") (pinfunction "B_B") (pintype "passive"))
      (node (ref "R69") (pin "1") (pinfunction "1_1") (pintype "passive"))
    )
    (net (code "139") (name "Net-(Q42-PadE)") (class "Default")
      (node (ref "Q42") (pin "E") (pinfunction "E_E") (pintype "passive"))
      (node (ref "R70") (pin "2") (pinfunction "2_2") (pintype "passive"))
    )
    (net (code "140") (name "Net-(Q43-PadE)") (class "Default")
      (node (ref "Q43") (pin "E") (pinfunction "E_E") (pintype "passive"))
      (node (ref "R71") (pin "1") (pinfunction "1_1") (pintype "passive"))
    )
    (net (code "141") (name "Net-(Q44-PadE)") (class "Default")
      (node (ref "Q44") (pin "E") (pinfunction "E_E") (pintype "passive"))
      (node (ref "R72") (pin "2") (pinfunction "2_2") (pintype "passive"))
    )
    (net (code "142") (name "Net-(Q46-PadE)") (class "Default")
      (node (ref "Q46") (pin "E") (pinfunction "E_E") (pintype "passive"))
      (node (ref "Q48") (pin "B") (pinfunction "B_B") (pintype "passive"))
      (node (ref "R77") (pin "2") (pinfunction "2_2") (pintype "passive"))
    )
    (net (code "143") (name "Net-(Q47-PadE)") (class "Default")
      (node (ref "Q47") (pin "E") (pinfunction "E_E") (pintype "passive"))
      (node (ref "Q49") (pin "B") (pinfunction "B_B") (pintype "passive"))
      (node (ref "R77") (pin "1") (pinfunction "1_1") (pintype "passive"))
    )
    (net (code "144") (name "Net-(Q48-PadE)") (class "Default")
      (node (ref "Q48") (pin "E") (pinfunction "E_E") (pintype "passive"))
      (node (ref "Q50") (pin "B") (pinfunction "B_B") (pintype "passive"))
      (node (ref "R78") (pin "2") (pinfunction "2_2") (pintype "passive"))
    )
    (net (code "145") (name "Net-(Q49-PadE)") (class "Default")
      (node (ref "Q49") (pin "E") (pinfunction "E_E") (pintype "passive"))
      (node (ref "Q51") (pin "B") (pinfunction "B_B") (pintype "passive"))
      (node (ref "R78") (pin "1") (pinfunction "1_1") (pintype "passive"))
    )
    (net (code "146") (name "Net-(Q50-PadE)") (class "Default")
      (node (ref "Q50") (pin "E") (pinfunction "E_E") (pintype "passive"))
      (node (ref "R80") (pin "2") (pinfunction "2_2") (pintype "passive"))
    )
    (net (code "147") (name "Net-(Q51-PadE)") (class "Default")
      (node (ref "Q51") (pin "E") (pinfunction "E_E") (pintype "passive"))
      (node (ref "R81") (pin "1") (pinfunction "1_1") (pintype "passive"))
    )
    (net (code "148") (name "Net-(Q52-PadE)") (class "Default")
      (node (ref "Q52") (pin "E") (pinfunction "E_E") (pintype "passive"))
      (node (ref "R86") (pin "1") (pinfunction "1_1") (pintype "passive"))
    )
    (net (code "149") (name "Net-(Q53-PadC)") (class "Default")
      (node (ref "Q53") (pin "C") (pinfunction "C_C") (pintype "passive"))
      (node (ref "Q58") (pin "E") (pinfunction "E_E") (pintype "passive"))
      (node (ref "R92") (pin "1") (pinfunction "1_1") (pintype "passive"))
    )
    (net (code "150") (name "Net-(Q53-PadE)") (class "Default")
      (node (ref "Q53") (pin "E") (pinfunction "E_E") (pintype "passive"))
      (node (ref "R87") (pin "1") (pinfunction "1_1") (pintype "passive"))
    )
    (net (code "151") (name "Net-(Q54-PadC)") (class "Default")
      (node (ref "Q54") (pin "C") (pinfunction "C_C") (pintype "passive"))
      (node (ref "Q57") (pin "E") (pinfunction "E_E") (pintype "passive"))
      (node (ref "R91") (pin "2") (pinfunction "2_2") (pintype "passive"))
    )
    (net (code "152") (name "Net-(Q54-PadE)") (class "Default")
      (node (ref "Q54") (pin "E") (pinfunction "E_E") (pintype "passive"))
      (node (ref "R88") (pin "2") (pinfunction "2_2") (pintype "passive"))
    )
    (net (code "153") (name "Net-(Q55-PadE)") (class "Default")
      (node (ref "Q55") (pin "E") (pinfunction "E_E") (pintype "passive"))
      (node (ref "R89") (pin "2") (pinfunction "2_2") (pintype "passive"))
    )
    (net (code "154") (name "Net-(Q56-PadC)") (class "Default")
      (node (ref "Q56") (pin "C") (pinfunction "C_C") (pintype "passive"))
      (node (ref "Q60") (pin "C") (pinfunction "C_C") (pintype "passive"))
      (node (ref "Q63") (pin "B") (pinfunction "B_B") (pintype "passive"))
    )
    (net (code "155") (name "Net-(Q56-PadE)") (class "Default")
      (node (ref "Q56") (pin "E") (pinfunction "E_E") (pintype "passive"))
      (node (ref "Q57") (pin "C") (pinfunction "C_C") (pintype "passive"))
    )
    (net (code "156") (name "Net-(Q58-PadC)") (class "Default")
      (node (ref "Q58") (pin "C") (pinfunction "C_C") (pintype "passive"))
      (node (ref "Q59") (pin "E") (pinfunction "E_E") (pintype "passive"))
    )
    (net (code "157") (name "Net-(Q59-PadC)") (class "Default")
      (node (ref "Q59") (pin "C") (pinfunction "C_C") (pintype "passive"))
      (node (ref "Q61") (pin "C") (pinfunction "C_C") (pintype "passive"))
      (node (ref "Q64") (pin "B") (pinfunction "B_B") (pintype "passive"))
    )
    (net (code "158") (name "Net-(Q60-PadB)") (class "Default")
      (node (ref "Q60") (pin "B") (pinfunction "B_B") (pintype "passive"))
      (node (ref "Q62") (pin "B") (pinfunction "B_B") (pintype "passive"))
      (node (ref "Q62") (pin "C") (pinfunction "C_C") (pintype "passive"))
      (node (ref "Q63") (pin "E") (pinfunction "E_E") (pintype "passive"))
    )
    (net (code "159") (name "Net-(Q60-PadE)") (class "Default")
      (node (ref "Q60") (pin "E") (pinfunction "E_E") (pintype "passive"))
      (node (ref "R90") (pin "1") (pinfunction "1_1") (pintype "passive"))
    )
    (net (code "160") (name "Net-(Q61-PadB)") (class "Default")
      (node (ref "Q61") (pin "B") (pinfunction "B_B") (pintype "passive"))
      (node (ref "Q64") (pin "E") (pinfunction "E_E") (pintype "passive"))
      (node (ref "Q65") (pin "B") (pinfunction "B_B") (pintype "passive"))
      (node (ref "Q65") (pin "C") (pinfunction "C_C") (pintype "passive"))
    )
    (net (code "161") (name "Net-(Q61-PadE)") (class "Default")
      (node (ref "Q61") (pin "E") (pinfunction "E_E") (pintype "passive"))
      (node (ref "R93") (pin "2") (pinfunction "2_2") (pintype "passive"))
    )
    (net (code "162") (name "Net-(Q63-PadC)") (class "Default")
      (node (ref "Q63") (pin "C") (pinfunction "C_C") (pintype "passive"))
      (node (ref "Q66") (pin "E") (pinfunction "E_E") (pintype "passive"))
    )
    (net (code "163") (name "Net-(Q64-PadC)") (class "Default")
      (node (ref "Q64") (pin "C") (pinfunction "C_C") (pintype "passive"))
      (node (ref "Q67") (pin "E") (pinfunction "E_E") (pintype "passive"))
    )
    (net (code "164") (name "Net-(Q68-PadB)") (class "Default")
      (node (ref "Q68") (pin "B") (pinfunction "B_B") (pintype "passive"))
      (node (ref "Q68") (pin "C") (pinfunction "C_C") (pintype "passive"))
      (node (ref "Q70") (pin "B") (pinfunction "B_B") (pintype "passive"))
      (node (ref "R100") (pin "2") (pinfunction "2_2") (pintype "passive"))
    )
    (net (code "165") (name "Net-(Q68-PadE)") (class "Default")
      (node (ref "Q68") (pin "E") (pinfunction "E_E") (pintype "passive"))
      (node (ref "R99") (pin "1") (pinfunction "1_1") (pintype "passive"))
    )
    (net (code "166") (name "Net-(Q69-PadB)") (class "Default")
      (node (ref "Q69") (pin "B") (pinfunction "B_B") (pintype "passive"))
      (node (ref "Q69") (pin "C") (pinfunction "C_C") (pintype "passive"))
      (node (ref "Q71") (pin "B") (pinfunction "B_B") (pintype "passive"))
      (node (ref "R101") (pin "1") (pinfunction "1_1") (pintype "passive"))
    )
    (net (code "167") (name "Net-(Q69-PadE)") (class "Default")
      (node (ref "Q69") (pin "E") (pinfunction "E_E") (pintype "passive"))
      (node (ref "R102") (pin "2") (pinfunction "2_2") (pintype "passive"))
    )
    (net (code "168") (name "Net-(Q70-PadE)") (class "Default")
      (node (ref "Q70") (pin "E") (pinfunction "E_E") (pintype "passive"))
      (node (ref "R103") (pin "1") (pinfunction "1_1") (pintype "passive"))
    )
    (net (code "169") (name "Net-(Q71-PadE)") (class "Default")
      (node (ref "Q71") (pin "E") (pinfunction "E_E") (pintype "passive"))
      (node (ref "R104") (pin "2") (pinfunction "2_2") (pintype "passive"))
    )
    (net (code "170") (name "Net-(Q73-PadE)") (class "Default")
      (node (ref "Q73") (pin "E") (pinfunction "E_E") (pintype "passive"))
      (node (ref "Q75") (pin "B") (pinfunction "B_B") (pintype "passive"))
      (node (ref "R109") (pin "2") (pinfunction "2_2") (pintype "passive"))
    )
    (net (code "171") (name "Net-(Q74-PadE)") (class "Default")
      (node (ref "Q74") (pin "E") (pinfunction "E_E") (pintype "passive"))
      (node (ref "Q76") (pin "B") (pinfunction "B_B") (pintype "passive"))
      (node (ref "R109") (pin "1") (pinfunction "1_1") (pintype "passive"))
    )
    (net (code "172") (name "Net-(Q75-PadE)") (class "Default")
      (node (ref "Q75") (pin "E") (pinfunction "E_E") (pintype "passive"))
      (node (ref "Q77") (pin "B") (pinfunction "B_B") (pintype "passive"))
      (node (ref "R110") (pin "2") (pinfunction "2_2") (pintype "passive"))
    )
    (net (code "173") (name "Net-(Q76-PadE)") (class "Default")
      (node (ref "Q76") (pin "E") (pinfunction "E_E") (pintype "passive"))
      (node (ref "Q78") (pin "B") (pinfunction "B_B") (pintype "passive"))
      (node (ref "R110") (pin "1") (pinfunction "1_1") (pintype "passive"))
    )
    (net (code "174") (name "Net-(Q77-PadE)") (class "Default")
      (node (ref "Q77") (pin "E") (pinfunction "E_E") (pintype "passive"))
      (node (ref "R112") (pin "2") (pinfunction "2_2") (pintype "passive"))
    )
    (net (code "175") (name "Net-(Q78-PadE)") (class "Default")
      (node (ref "Q78") (pin "E") (pinfunction "E_E") (pintype "passive"))
      (node (ref "R113") (pin "1") (pinfunction "1_1") (pintype "passive"))
    )
    (net (code "176") (name "Net-(Q79-PadC)") (class "Default")
      (node (ref "Q79") (pin "C") (pinfunction "C_C") (pintype "passive"))
      (node (ref "Q81") (pin "B") (pinfunction "B_B") (pintype "passive"))
      (node (ref "Q81") (pin "C") (pinfunction "C_C") (pintype "passive"))
      (node (ref "Q83") (pin "B") (pinfunction "B_B") (pintype "passive"))
    )
    (net (code "177") (name "Net-(Q79-PadE)") (class "Default")
      (node (ref "Q79") (pin "E") (pinfunction "E_E") (pintype "passive"))
      (node (ref "R117") (pin "1") (pinfunction "1_1") (pintype "passive"))
    )
    (net (code "178") (name "Net-(Q80-PadC)") (class "Default")
      (node (ref "Q80") (pin "C") (pinfunction "C_C") (pintype "passive"))
      (node (ref "Q82") (pin "B") (pinfunction "B_B") (pintype "passive"))
      (node (ref "Q82") (pin "C") (pinfunction "C_C") (pintype "passive"))
      (node (ref "Q84") (pin "B") (pinfunction "B_B") (pintype "passive"))
    )
    (net (code "179") (name "Net-(Q80-PadE)") (class "Default")
      (node (ref "Q80") (pin "E") (pinfunction "E_E") (pintype "passive"))
      (node (ref "R118") (pin "2") (pinfunction "2_2") (pintype "passive"))
    )
    (net (code "180") (name "Net-(Q83-PadE)") (class "Default")
      (node (ref "Q83") (pin "E") (pinfunction "E_E") (pintype "passive"))
      (node (ref "R119") (pin "2") (pinfunction "2_2") (pintype "passive"))
    )
    (net (code "181") (name "Net-(Q84-PadE)") (class "Default")
      (node (ref "Q84") (pin "E") (pinfunction "E_E") (pintype "passive"))
      (node (ref "R122") (pin "1") (pinfunction "1_1") (pintype "passive"))
    )
    (net (code "182") (name "Net-(Q85-PadB)") (class "Default")
      (node (ref "Q85") (pin "B") (pinfunction "B_B") (pintype "passive"))
      (node (ref "R123") (pin "2") (pinfunction "2_2") (pintype "passive"))
    )
    (net (code "183") (name "Net-(Q85-PadE)") (class "Default")
      (node (ref "Q85") (pin "E") (pinfunction "E_E") (pintype "passive"))
      (node (ref "R120") (pin "2") (pinfunction "2_2") (pintype "passive"))
    )
    (net (code "184") (name "Net-(Q86-PadB)") (class "Default")
      (node (ref "Q86") (pin "B") (pinfunction "B_B") (pintype "passive"))
      (node (ref "R124") (pin "2") (pinfunction "2_2") (pintype "passive"))
    )
    (net (code "185") (name "Net-(Q86-PadE)") (class "Default")
      (node (ref "Q86") (pin "E") (pinfunction "E_E") (pintype "passive"))
      (node (ref "R121") (pin "1") (pinfunction "1_1") (pintype "passive"))
    )
    (net (code "186") (name "Net-(Q87-PadE)") (class "Default")
      (node (ref "Q87") (pin "E") (pinfunction "E_E") (pintype "passive"))
      (node (ref "Q89") (pin "B") (pinfunction "B_B") (pintype "passive"))
    )
    (net (code "187") (name "Net-(Q88-PadE)") (class "Default")
      (node (ref "Q88") (pin "E") (pinfunction "E_E") (pintype "passive"))
      (node (ref "Q90") (pin "B") (pinfunction "B_B") (pintype "passive"))
    )
    (net (code "188") (name "Net-(Q91-PadS)") (class "Default")
      (node (ref "Q91") (pin "S") (pinfunction "S_S") (pintype "passive"))
      (node (ref "R125") (pin "2") (pinfunction "2_2") (pintype "passive"))
    )
    (net (code "189") (name "Net-(Q92-PadS)") (class "Default")
      (node (ref "Q92") (pin "S") (pinfunction "S_S") (pintype "passive"))
      (node (ref "R126") (pin "2") (pinfunction "2_2") (pintype "passive"))
    )
    (net (code "190") (name "Net-(R1-S)") (class "Default")
      (node (ref "R1") (pin "2") (pinfunction "S_2") (pintype "passive"))
      (node (ref "R2") (pin "2") (pinfunction "2_2") (pintype "passive"))
    )
    (net (code "191") (name "Net-(R2-Pad1)") (class "Default")
      (node (ref "R2") (pin "1") (pinfunction "1_1") (pintype "passive"))
      (node (ref "R3") (pin "1") (pinfunction "1_1") (pintype "passive"))
      (node (ref "R4") (pin "2") (pinfunction "2_2") (pintype "passive"))
    )
    (net (code "192") (name "Net-(R59-Pad1)") (class "Default")
      (node (ref "R59") (pin "1") (pinfunction "1_1") (pintype "passive"))
      (node (ref "R60") (pin "2") (pinfunction "2_2") (pintype "passive"))
      (node (ref "R63") (pin "2") (pinfunction "2_2") (pintype "passive"))
      (node (ref "R66") (pin "1") (pinfunction "1_1") (pintype "passive"))
    )
    (net (code "193") (name "Net-(R74-A)") (class "Default")
      (node (ref "C18") (pin "2") (pinfunction "2_2") (pintype "passive"))
      (node (ref "C20") (pin "1") (pinfunction "1_1") (pintype "passive"))
      (node (ref "Q40") (pin "C") (pinfunction "C_C") (pintype "passive"))
      (node (ref "Q44") (pin "C") (pinfunction "C_C") (pintype "passive"))
      (node (ref "Q45") (pin "E") (pinfunction "E_E") (pintype "passive"))
      (node (ref "Q47") (pin "B") (pinfunction "B_B") (pintype "passive"))
      (node (ref "R74") (pin "1") (pinfunction "A_1") (pintype "passive"))
      (node (ref "R74") (pin "2") (pinfunction "S_2") (pintype "passive"))
      (node (ref "R76") (pin "2") (pinfunction "2_2") (pintype "passive"))
    )
    (net (code "194") (name "Net-(R74-E)") (class "Default")
      (node (ref "Q45") (pin "B") (pinfunction "B_B") (pintype "passive"))
      (node (ref "R73") (pin "1") (pinfunction "1_1") (pintype "passive"))
      (node (ref "R74") (pin "3") (pinfunction "E_3") (pintype "passive"))
    )
    (net (code "195") (name "Net-(R91-Pad1)") (class "Default")
      (node (ref "R91") (pin "1") (pinfunction "1_1") (pintype "passive"))
      (node (ref "R92") (pin "2") (pinfunction "2_2") (pintype "passive"))
      (node (ref "R95") (pin "2") (pinfunction "2_2") (pintype "passive"))
      (node (ref "R98") (pin "1") (pinfunction "1_1") (pintype "passive"))
    )
    (net (code "196") (name "Net-(R106-A)") (class "Default")
      (node (ref "C28") (pin "2") (pinfunction "2_2") (pintype "passive"))
      (node (ref "C30") (pin "1") (pinfunction "1_1") (pintype "passive"))
      (node (ref "Q67") (pin "C") (pinfunction "C_C") (pintype "passive"))
      (node (ref "Q71") (pin "C") (pinfunction "C_C") (pintype "passive"))
      (node (ref "Q72") (pin "E") (pinfunction "E_E") (pintype "passive"))
      (node (ref "Q74") (pin "B") (pinfunction "B_B") (pintype "passive"))
      (node (ref "R106") (pin "1") (pinfunction "A_1") (pintype "passive"))
      (node (ref "R106") (pin "2") (pinfunction "S_2") (pintype "passive"))
      (node (ref "R108") (pin "2") (pinfunction "2_2") (pintype "passive"))
    )
    (net (code "197") (name "Net-(R106-E)") (class "Default")
      (node (ref "Q72") (pin "B") (pinfunction "B_B") (pintype "passive"))
      (node (ref "R105") (pin "1") (pinfunction "1_1") (pintype "passive"))
      (node (ref "R106") (pin "3") (pinfunction "E_3") (pintype "passive"))
    )
    (net (code "198") (name "OUT+") (class "Default")
      (node (ref "PAD1") (pin "P$1") (pinfunction "P$1_P$1") (pintype "bidirectional"))
      (node (ref "R66") (pin "2") (pinfunction "2_2") (pintype "passive"))
      (node (ref "R80") (pin "1") (pinfunction "1_1") (pintype "passive"))
      (node (ref "R81") (pin "2") (pinfunction "2_2") (pintype "passive"))
      (node (ref "R82") (pin "1") (pinfunction "1_1") (pintype "passive"))
    )
    (net (code "199") (name "OUT-") (class "Default")
      (node (ref "PAD2") (pin "P$1") (pinfunction "P$1_P$1") (pintype "bidirectional"))
      (node (ref "R112") (pin "1") (pinfunction "1_1") (pintype "passive"))
      (node (ref "R113") (pin "2") (pinfunction "2_2") (pintype "passive"))
      (node (ref "R114") (pin "1") (pinfunction "1_1") (pintype "passive"))
      (node (ref "R98") (pin "2") (pinfunction "2_2") (pintype "passive"))
    )
    (net (code "200") (name "UOUT+") (class "Default")
      (node (ref "Q10") (pin "B") (pinfunction "B_B") (pintype "passive"))
      (node (ref "Q5") (pin "6") (pinfunction "C_6") (pintype "passive"))
      (node (ref "Q6") (pin "6") (pinfunction "C_6") (pintype "passive"))
      (node (ref "Q9") (pin "B") (pinfunction "B_B") (pintype "passive"))
      (node (ref "R11") (pin "2") (pinfunction "2_2") (pintype "passive"))
      (node (ref "R21") (pin "2") (pinfunction "2_2") (pintype "passive"))
    )
    (net (code "201") (name "UOUT-") (class "Default")
      (node (ref "Q17") (pin "B") (pinfunction "B_B") (pintype "passive"))
      (node (ref "Q18") (pin "B") (pinfunction "B_B") (pintype "passive"))
      (node (ref "Q5") (pin "4") (pinfunction "C_4") (pintype "passive"))
      (node (ref "Q6") (pin "4") (pinfunction "C_4") (pintype "passive"))
      (node (ref "R20") (pin "2") (pinfunction "2_2") (pintype "passive"))
      (node (ref "R36") (pin "2") (pinfunction "2_2") (pintype "passive"))
    )
    (net (code "202") (name "V+") (class "Default")
      (node (ref "C1") (pin "+") (pinfunction "+_+") (pintype "passive"))
      (node (ref "C11") (pin "1") (pinfunction "1_1") (pintype "passive"))
      (node (ref "C14") (pin "2") (pinfunction "2_2") (pintype "passive"))
      (node (ref "C23") (pin "1") (pinfunction "1_1") (pintype "passive"))
      (node (ref "C25") (pin "+") (pinfunction "+_+") (pintype "passive"))
      (node (ref "C3") (pin "2") (pinfunction "2_2") (pintype "passive"))
      (node (ref "C33") (pin "1") (pinfunction "1_1") (pintype "passive"))
      (node (ref "C35") (pin "+") (pinfunction "+_+") (pintype "passive"))
      (node (ref "C45") (pin "2") (pinfunction "2_2") (pintype "passive"))
      (node (ref "C5") (pin "+") (pinfunction "+_+") (pintype "passive"))
      (node (ref "C53") (pin "1") (pinfunction "1_1") (pintype "passive"))
      (node (ref "C55") (pin "2") (pinfunction "2_2") (pintype "passive"))
      (node (ref "C7") (pin "+") (pinfunction "+_+") (pintype "passive"))
      (node (ref "C9") (pin "1") (pinfunction "1_1") (pintype "passive"))
      (node (ref "D1") (pin "A") (pinfunction "A_A") (pintype "passive"))
      (node (ref "D15") (pin "A") (pinfunction "A_A") (pintype "passive"))
      (node (ref "D7") (pin "A") (pinfunction "A_A") (pintype "passive"))
      (node (ref "IC1") (pin "7") (pinfunction "V+_7") (pintype "power_in"))
      (node (ref "IC2") (pin "7") (pinfunction "V+_7") (pintype "power_in"))
      (node (ref "IC3") (pin "7") (pinfunction "V+_7") (pintype "power_in"))
      (node (ref "IC4") (pin "7") (pinfunction "V+_7") (pintype "power_in"))
      (node (ref "IC6") (pin "7") (pinfunction "V+_7") (pintype "power_in"))
      (node (ref "LED1") (pin "A") (pinfunction "A_A") (pintype "passive"))
      (node (ref "LED3") (pin "A") (pinfunction "A_A") (pintype "passive"))
      (node (ref "LED5") (pin "A") (pinfunction "A_A") (pintype "passive"))
      (node (ref "LED7") (pin "A") (pinfunction "A_A") (pintype "passive"))
      (node (ref "Q13") (pin "C") (pinfunction "C_C") (pintype "passive"))
      (node (ref "Q15") (pin "C") (pinfunction "C_C") (pintype "passive"))
      (node (ref "Q17") (pin "C") (pinfunction "C_C") (pintype "passive"))
      (node (ref "Q21") (pin "C") (pinfunction "C_C") (pintype "passive"))
      (node (ref "Q23") (pin "C") (pinfunction "C_C") (pintype "passive"))
      (node (ref "Q46") (pin "C") (pinfunction "C_C") (pintype "passive"))
      (node (ref "Q48") (pin "C") (pinfunction "C_C") (pintype "passive"))
      (node (ref "Q50") (pin "C") (pinfunction "C_C") (pintype "passive"))
      (node (ref "Q73") (pin "C") (pinfunction "C_C") (pintype "passive"))
      (node (ref "Q75") (pin "C") (pinfunction "C_C") (pintype "passive"))
      (node (ref "Q77") (pin "C") (pinfunction "C_C") (pintype "passive"))
      (node (ref "Q89") (pin "E") (pinfunction "E_E") (pintype "passive"))
      (node (ref "Q9") (pin "C") (pinfunction "C_C") (pintype "passive"))
      (node (ref "Q91") (pin "D") (pinfunction "D_D") (pintype "passive"))
      (node (ref "R1") (pin "3") (pinfunction "E_3") (pintype "passive"))
      (node (ref "R103") (pin "2") (pinfunction "2_2") (pintype "passive"))
      (node (ref "R12") (pin "2") (pinfunction "2_2") (pintype "passive"))
      (node (ref "R127") (pin "2") (pinfunction "2_2") (pintype "passive"))
      (node (ref "R131") (pin "2") (pinfunction "2_2") (pintype "passive"))
      (node (ref "R18") (pin "2") (pinfunction "2_2") (pintype "passive"))
      (node (ref "R23") (pin "2") (pinfunction "2_2") (pintype "passive"))
      (node (ref "R38") (pin "2") (pinfunction "2_2") (pintype "passive"))
      (node (ref "R5") (pin "2") (pinfunction "2_2") (pintype "passive"))
      (node (ref "R54") (pin "2") (pinfunction "2_2") (pintype "passive"))
      (node (ref "R58") (pin "2") (pinfunction "2_2") (pintype "passive"))
      (node (ref "R62") (pin "2") (pinfunction "2_2") (pintype "passive"))
      (node (ref "R67") (pin "2") (pinfunction "2_2") (pintype "passive"))
      (node (ref "R71") (pin "2") (pinfunction "2_2") (pintype "passive"))
      (node (ref "R86") (pin "2") (pinfunction "2_2") (pintype "passive"))
      (node (ref "R90") (pin "2") (pinfunction "2_2") (pintype "passive"))
      (node (ref "R94") (pin "2") (pinfunction "2_2") (pintype "passive"))
      (node (ref "R99") (pin "2") (pinfunction "2_2") (pintype "passive"))
      (node (ref "X2") (pin "1") (pinfunction "S_1") (pintype "passive"))
    )
    (net (code "203") (name "V-") (class "Default")
      (node (ref "C10") (pin "2") (pinfunction "2_2") (pintype "passive"))
      (node (ref "C12") (pin "2") (pinfunction "2_2") (pintype "passive"))
      (node (ref "C15") (pin "1") (pinfunction "1_1") (pintype "passive"))
      (node (ref "C2") (pin "-") (pinfunction "-_-") (pintype "passive"))
      (node (ref "C24") (pin "2") (pinfunction "2_2") (pintype "passive"))
      (node (ref "C26") (pin "-") (pinfunction "-_-") (pintype "passive"))
      (node (ref "C34") (pin "2") (pinfunction "2_2") (pintype "passive"))
      (node (ref "C36") (pin "-") (pinfunction "-_-") (pintype "passive"))
      (node (ref "C4") (pin "1") (pinfunction "1_1") (pintype "passive"))
      (node (ref "C46") (pin "1") (pinfunction "1_1") (pintype "passive"))
      (node (ref "C54") (pin "2") (pinfunction "2_2") (pintype "passive"))
      (node (ref "C56") (pin "1") (pinfunction "1_1") (pintype "passive"))
      (node (ref "C6") (pin "-") (pinfunction "-_-") (pintype "passive"))
      (node (ref "C8") (pin "-") (pinfunction "-_-") (pintype "passive"))
      (node (ref "D10") (pin "C") (pinfunction "C_C") (pintype "passive"))
      (node (ref "D16") (pin "C") (pinfunction "C_C") (pintype "passive"))
      (node (ref "D4") (pin "C") (pinfunction "C_C") (pintype "passive"))
      (node (ref "IC1") (pin "4") (pinfunction "V-_4") (pintype "power_in"))
      (node (ref "IC2") (pin "4") (pinfunction "V-_4") (pintype "power_in"))
      (node (ref "IC3") (pin "4") (pinfunction "V-_4") (pintype "power_in"))
      (node (ref "IC4") (pin "4") (pinfunction "V-_4") (pintype "power_in"))
      (node (ref "IC5") (pin "4") (pinfunction "V-_4") (pintype "power_in"))
      (node (ref "LED2") (pin "C") (pinfunction "C_C") (pintype "passive"))
      (node (ref "LED4") (pin "C") (pinfunction "C_C") (pintype "passive"))
      (node (ref "LED6") (pin "C") (pinfunction "C_C") (pintype "passive"))
      (node (ref "LED8") (pin "C") (pinfunction "C_C") (pintype "passive"))
      (node (ref "Q10") (pin "C") (pinfunction "C_C") (pintype "passive"))
      (node (ref "Q14") (pin "C") (pinfunction "C_C") (pintype "passive"))
      (node (ref "Q16") (pin "C") (pinfunction "C_C") (pintype "passive"))
      (node (ref "Q18") (pin "C") (pinfunction "C_C") (pintype "passive"))
      (node (ref "Q22") (pin "C") (pinfunction "C_C") (pintype "passive"))
      (node (ref "Q24") (pin "C") (pinfunction "C_C") (pintype "passive"))
      (node (ref "Q47") (pin "C") (pinfunction "C_C") (pintype "passive"))
      (node (ref "Q49") (pin "C") (pinfunction "C_C") (pintype "passive"))
      (node (ref "Q51") (pin "C") (pinfunction "C_C") (pintype "passive"))
      (node (ref "Q74") (pin "C") (pinfunction "C_C") (pintype "passive"))
      (node (ref "Q76") (pin "C") (pinfunction "C_C") (pintype "passive"))
      (node (ref "Q78") (pin "C") (pinfunction "C_C") (pintype "passive"))
      (node (ref "Q90") (pin "E") (pinfunction "E_E") (pintype "passive"))
      (node (ref "Q92") (pin "G") (pinfunction "G_G") (pintype "passive"))
      (node (ref "R1") (pin "1") (pinfunction "A_1") (pintype "passive"))
      (node (ref "R102") (pin "1") (pinfunction "1_1") (pintype "passive"))
      (node (ref "R104") (pin "1") (pinfunction "1_1") (pintype "passive"))
      (node (ref "R126") (pin "1") (pinfunction "1_1") (pintype "passive"))
      (node (ref "R13") (pin "1") (pinfunction "1_1") (pintype "passive"))
      (node (ref "R130") (pin "1") (pinfunction "1_1") (pintype "passive"))
      (node (ref "R132") (pin "1") (pinfunction "1_1") (pintype "passive"))
      (node (ref "R19") (pin "1") (pinfunction "1_1") (pintype "passive"))
      (node (ref "R26") (pin "1") (pinfunction "1_1") (pintype "passive"))
      (node (ref "R41") (pin "1") (pinfunction "1_1") (pintype "passive"))
      (node (ref "R57") (pin "1") (pinfunction "1_1") (pintype "passive"))
      (node (ref "R61") (pin "1") (pinfunction "1_1") (pintype "passive"))
      (node (ref "R64") (pin "1") (pinfunction "1_1") (pintype "passive"))
      (node (ref "R7") (pin "1") (pinfunction "1_1") (pintype "passive"))
      (node (ref "R70") (pin "1") (pinfunction "1_1") (pintype "passive"))
      (node (ref "R72") (pin "1") (pinfunction "1_1") (pintype "passive"))
      (node (ref "R89") (pin "1") (pinfunction "1_1") (pintype "passive"))
      (node (ref "R93") (pin "1") (pinfunction "1_1") (pintype "passive"))
      (node (ref "R96") (pin "1") (pinfunction "1_1") (pintype "passive"))
      (node (ref "X2") (pin "3") (pinfunction "S_3") (pintype "passive"))
    )
    (net (code "204") (name "unconnected-(IC1-TRIM1-Pad1)") (class "Default")
      (node (ref "IC1") (pin "1") (pinfunction "TRIM1_1") (pintype "passive"))
    )
    (net (code "205") (name "unconnected-(IC1-TRIM2-Pad5)") (class "Default")
      (node (ref "IC1") (pin "5") (pinfunction "TRIM2_5") (pintype "passive"))
    )
    (net (code "206") (name "unconnected-(IC2-TRIM1-Pad1)") (class "Default")
      (node (ref "IC2") (pin "1") (pinfunction "TRIM1_1") (pintype "passive"))
    )
    (net (code "207") (name "unconnected-(IC2-TRIM2-Pad5)") (class "Default")
      (node (ref "IC2") (pin "5") (pinfunction "TRIM2_5") (pintype "passive"))
    )
    (net (code "208") (name "unconnected-(IC3-CMP1-Pad1)") (class "Default")
      (node (ref "IC3") (pin "1") (pinfunction "CMP1_1") (pintype "passive"))
    )
    (net (code "209") (name "unconnected-(IC3-CMP2-Pad8)") (class "Default")
      (node (ref "IC3") (pin "8") (pinfunction "CMP2_8") (pintype "passive"))
    )
    (net (code "210") (name "unconnected-(IC4-CMP1-Pad1)") (class "Default")
      (node (ref "IC4") (pin "1") (pinfunction "CMP1_1") (pintype "passive"))
    )
    (net (code "211") (name "unconnected-(IC4-CMP2-Pad8)") (class "Default")
      (node (ref "IC4") (pin "8") (pinfunction "CMP2_8") (pintype "passive"))
    )
    (net (code "212") (name "unconnected-(IC5-CMP1-Pad1)") (class "Default")
      (node (ref "IC5") (pin "1") (pinfunction "CMP1_1") (pintype "passive"))
    )
    (net (code "213") (name "unconnected-(IC5-CMP2-Pad8)") (class "Default")
      (node (ref "IC5") (pin "8") (pinfunction "CMP2_8") (pintype "passive"))
    )
    (net (code "214") (name "unconnected-(IC6-CMP1-Pad1)") (class "Default")
      (node (ref "IC6") (pin "1") (pinfunction "CMP1_1") (pintype "passive"))
    )
    (net (code "215") (name "unconnected-(IC6-CMP2-Pad8)") (class "Default")
      (node (ref "IC6") (pin "8") (pinfunction "CMP2_8") (pintype "passive"))
    )
  )
)
